# SH-03225-V0_5.net
KiCad netlist of a schematic drawn in Altium Designer
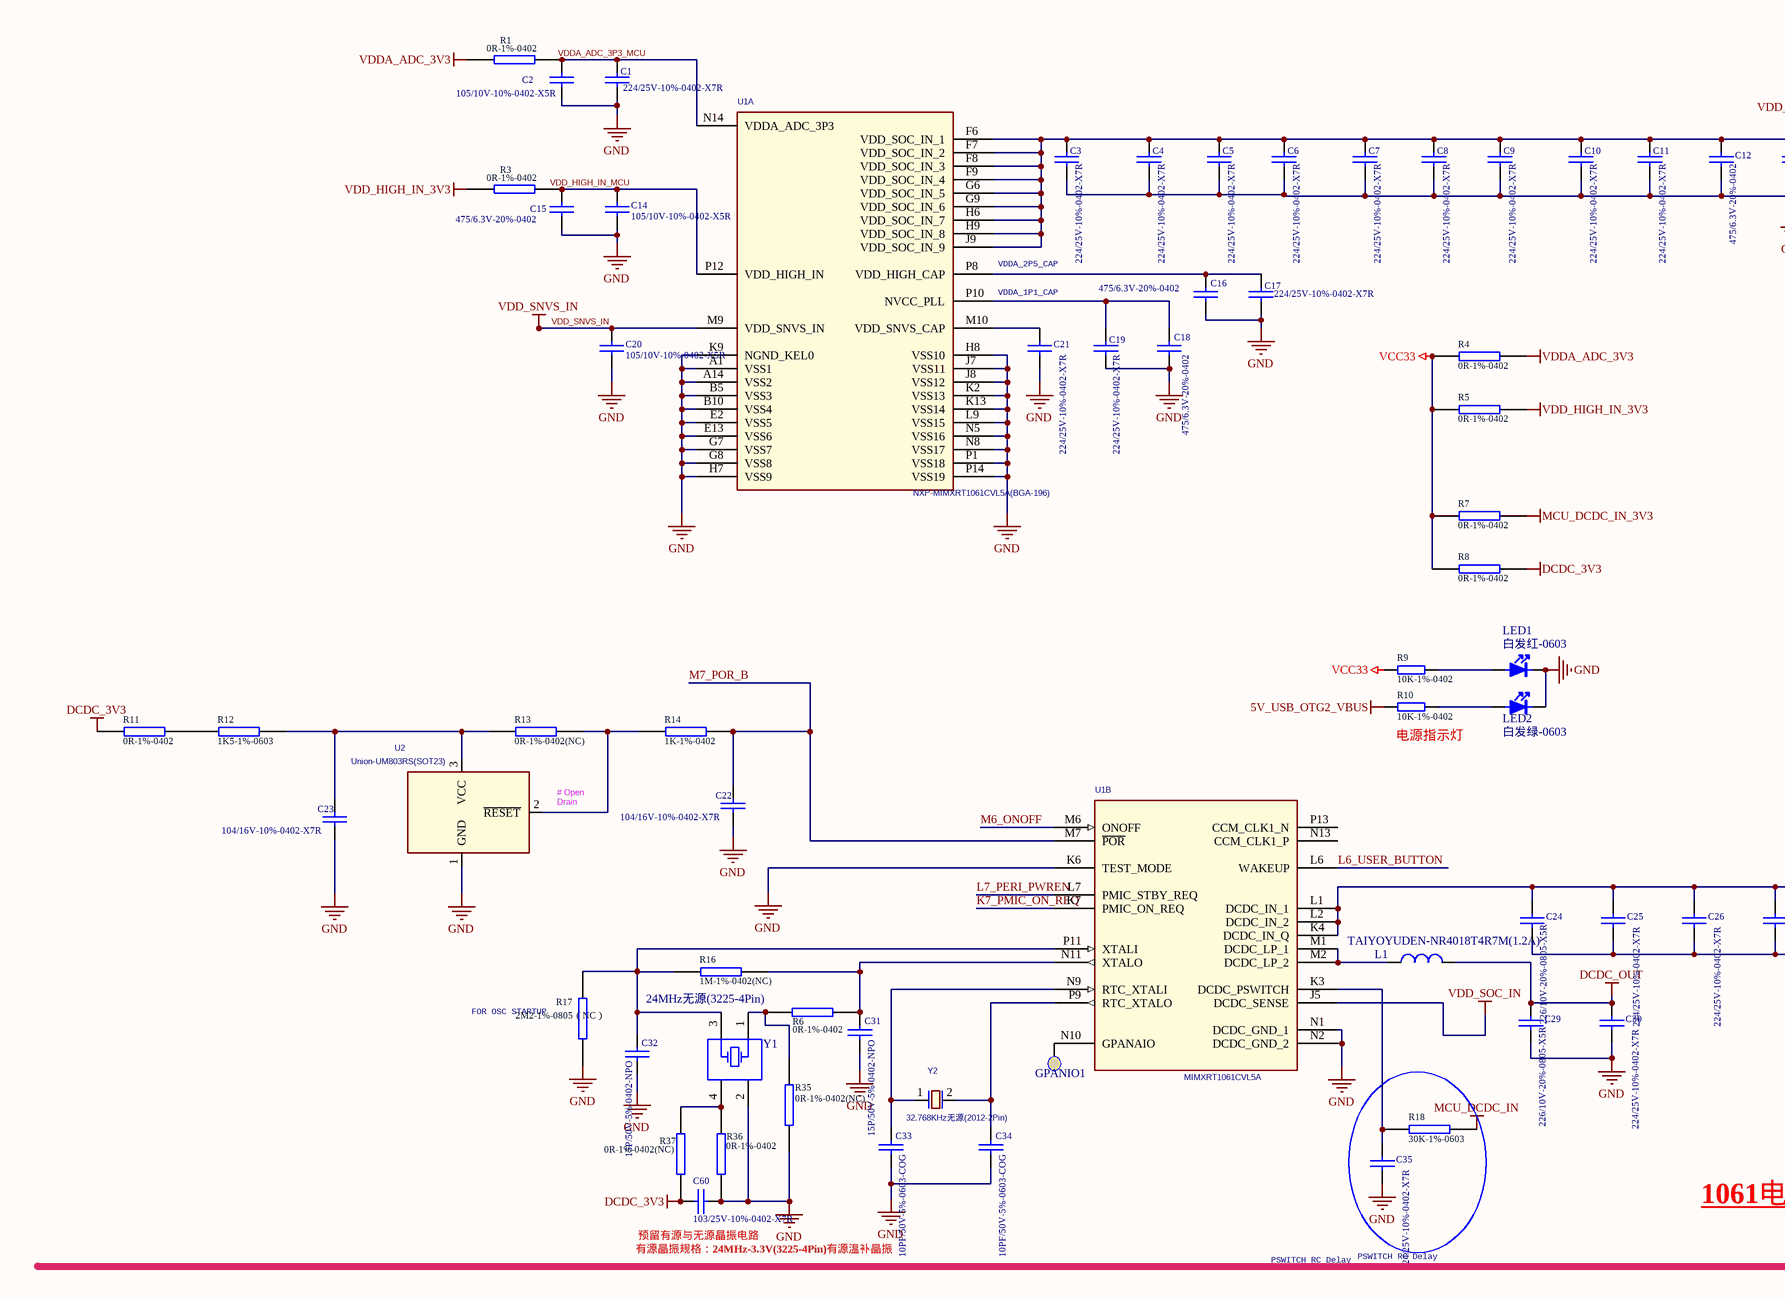
[diagram p0: SH-03225-V0.5.SchDoc, top left]
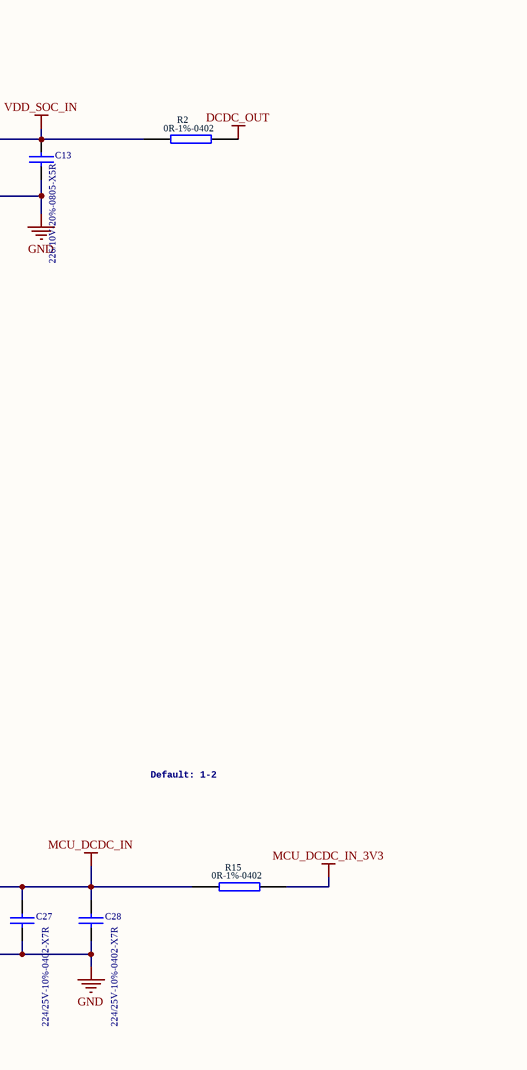
[diagram p1: SH-03225-V0.5.SchDoc, top middle]
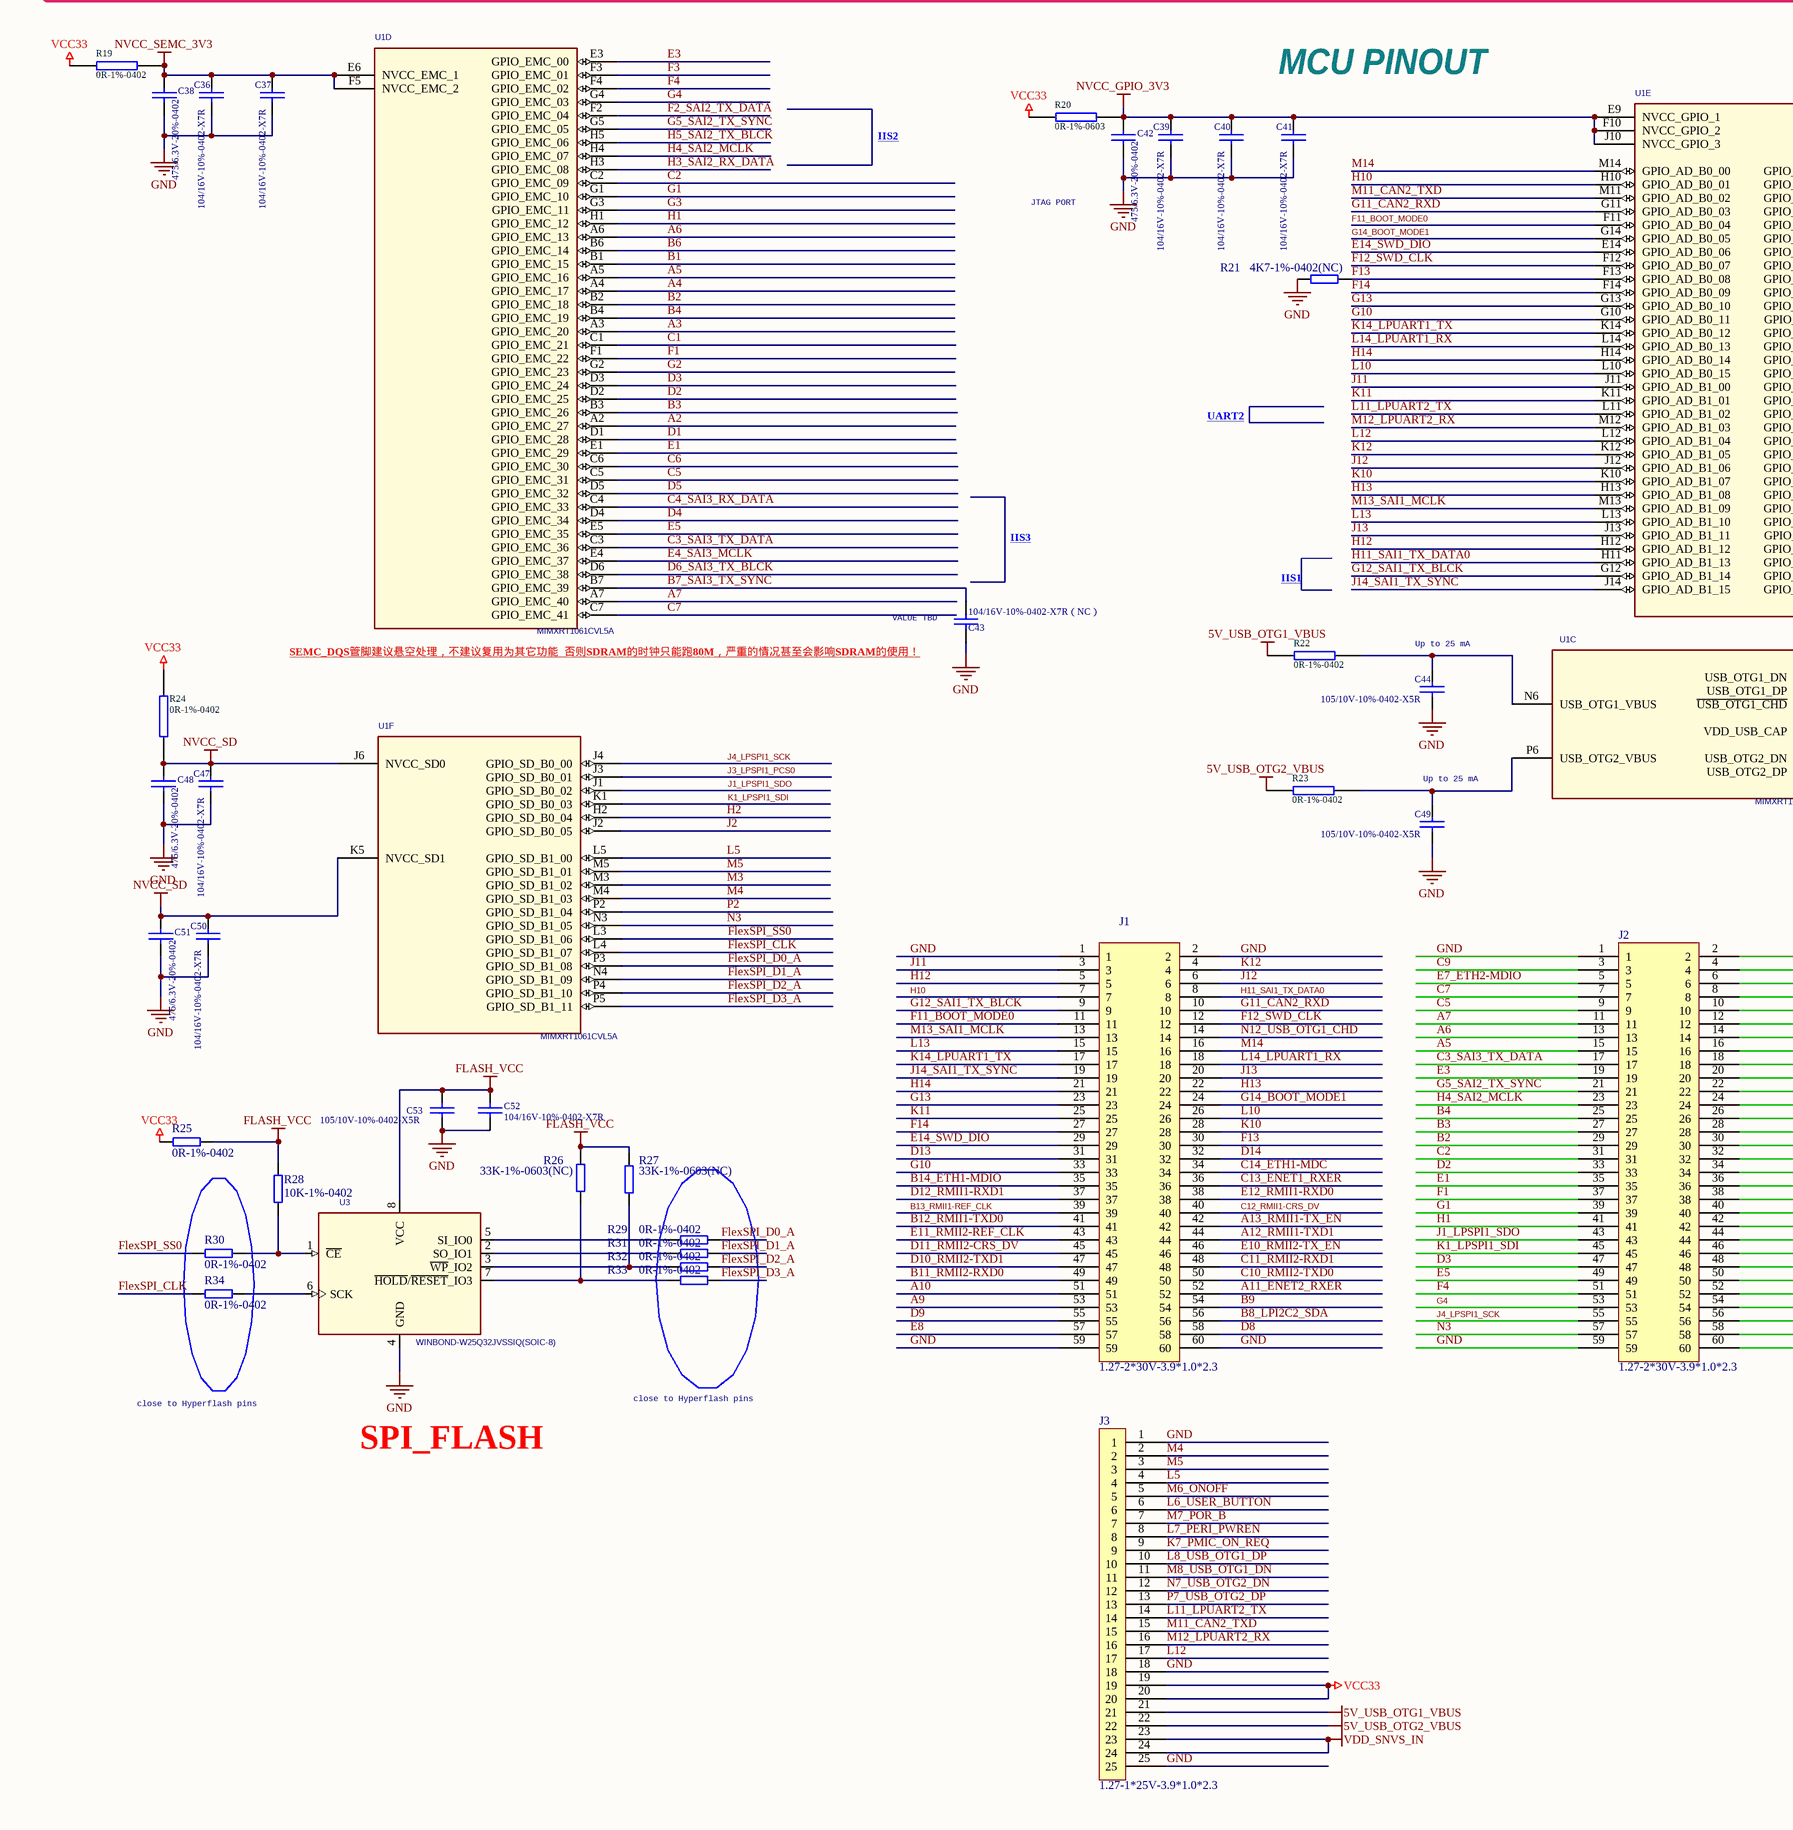
[diagram p2: SH-03225-V0.5.SchDoc, bottom left]
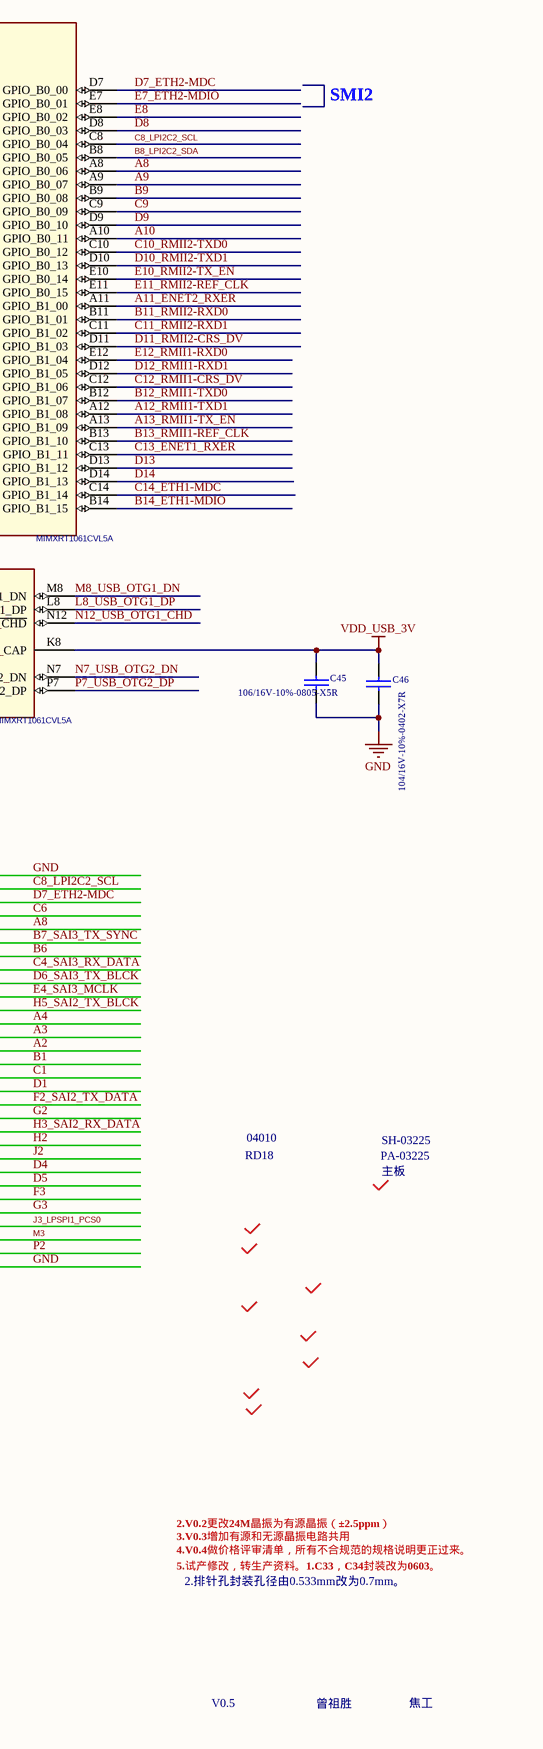
[diagram p3: SH-03225-V0.5.SchDoc, bottom middle]
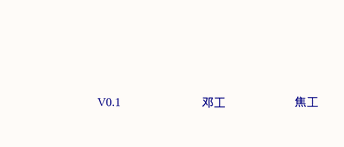
[diagram p4: SH-03225-V0.5.SchDoc, bottom right]

(export (version "E")
  (design (tool "Eeschema 10.0.6"))
  (components
    (comp (ref "C1")
      (value "224/25V-10%-0402-X7R")
      (footprint "BL-C0402")
      (description "Capacitor")
      (libsource (lib "*") (part "CAP"))
    )
    (comp (ref "C2")
      (value "105/10V-10%-0402-X5R")
      (footprint "BL-C0402")
      (description "Capacitor")
      (libsource (lib "*") (part "CAP"))
    )
    (comp (ref "C3")
      (value "224/25V-10%-0402-X7R")
      (footprint "BL-C0402")
      (description "Capacitor")
      (libsource (lib "*") (part "CAP"))
    )
    (comp (ref "C4")
      (value "224/25V-10%-0402-X7R")
      (footprint "BL-C0402")
      (description "Capacitor")
      (libsource (lib "*") (part "CAP"))
    )
    (comp (ref "C5")
      (value "224/25V-10%-0402-X7R")
      (footprint "BL-C0402")
      (description "Capacitor")
      (libsource (lib "*") (part "CAP"))
    )
    (comp (ref "C6")
      (value "224/25V-10%-0402-X7R")
      (footprint "BL-C0402")
      (description "Capacitor")
      (libsource (lib "*") (part "CAP"))
    )
    (comp (ref "C7")
      (value "224/25V-10%-0402-X7R")
      (footprint "BL-C0402")
      (description "Capacitor")
      (libsource (lib "*") (part "CAP"))
    )
    (comp (ref "C8")
      (value "224/25V-10%-0402-X7R")
      (footprint "BL-C0402")
      (description "Capacitor")
      (libsource (lib "*") (part "CAP"))
    )
    (comp (ref "C9")
      (value "224/25V-10%-0402-X7R")
      (footprint "BL-C0402")
      (description "Capacitor")
      (libsource (lib "*") (part "CAP"))
    )
    (comp (ref "C10")
      (value "224/25V-10%-0402-X7R")
      (footprint "BL-C0402")
      (description "Capacitor")
      (libsource (lib "*") (part "CAP"))
    )
    (comp (ref "C11")
      (value "224/25V-10%-0402-X7R")
      (footprint "BL-C0402")
      (description "Capacitor")
      (libsource (lib "*") (part "CAP"))
    )
    (comp (ref "C12")
      (value "475/6.3V-20%-0402")
      (footprint "BL-C0402")
      (description "Capacitor")
      (libsource (lib "*") (part "CAP"))
    )
    (comp (ref "C13")
      (value "226/10V-20%-0805-X5R")
      (footprint "BL-C0805")
      (description "Capacitor")
      (libsource (lib "*") (part "CAP"))
    )
    (comp (ref "C14")
      (value "105/10V-10%-0402-X5R")
      (footprint "BL-C0402")
      (description "Capacitor")
      (libsource (lib "*") (part "CAP"))
    )
    (comp (ref "C15")
      (value "475/6.3V-20%-0402")
      (footprint "BL-C0402")
      (description "Capacitor")
      (libsource (lib "*") (part "CAP"))
    )
    (comp (ref "C16")
      (value "475/6.3V-20%-0402")
      (footprint "BL-C0402")
      (description "Capacitor")
      (libsource (lib "*") (part "CAP"))
    )
    (comp (ref "C17")
      (value "224/25V-10%-0402-X7R")
      (footprint "BL-C0402")
      (description "Capacitor")
      (libsource (lib "*") (part "CAP"))
    )
    (comp (ref "C18")
      (value "475/6.3V-20%-0402")
      (footprint "BL-C0402")
      (description "Capacitor")
      (libsource (lib "*") (part "CAP"))
    )
    (comp (ref "C19")
      (value "224/25V-10%-0402-X7R")
      (footprint "BL-C0402")
      (description "Capacitor")
      (libsource (lib "*") (part "CAP"))
    )
    (comp (ref "C20")
      (value "105/10V-10%-0402-X5R")
      (footprint "BL-C0402")
      (description "Capacitor")
      (libsource (lib "*") (part "CAP"))
    )
    (comp (ref "C21")
      (value "224/25V-10%-0402-X7R")
      (footprint "BL-C0402")
      (description "Capacitor")
      (libsource (lib "*") (part "CAP"))
    )
    (comp (ref "C22")
      (value "104/16V-10%-0402-X7R")
      (footprint "BL-C0402")
      (description "Capacitor")
      (libsource (lib "*") (part "CAP"))
    )
    (comp (ref "C23")
      (value "104/16V-10%-0402-X7R")
      (footprint "BL-C0402")
      (description "Capacitor")
      (libsource (lib "*") (part "CAP"))
    )
    (comp (ref "C24")
      (value "226/10V-20%-0805-X5R")
      (footprint "BL-C0805")
      (description "Capacitor")
      (libsource (lib "*") (part "CAP"))
    )
    (comp (ref "C25")
      (value "224/25V-10%-0402-X7R")
      (footprint "BL-C0402")
      (description "Capacitor")
      (libsource (lib "*") (part "CAP"))
    )
    (comp (ref "C26")
      (value "224/25V-10%-0402-X7R")
      (footprint "BL-C0402")
      (description "Capacitor")
      (libsource (lib "*") (part "CAP"))
    )
    (comp (ref "C27")
      (value "224/25V-10%-0402-X7R")
      (footprint "BL-C0402")
      (description "Capacitor")
      (libsource (lib "*") (part "CAP"))
    )
    (comp (ref "C28")
      (value "224/25V-10%-0402-X7R")
      (footprint "BL-C0402")
      (description "Capacitor")
      (libsource (lib "*") (part "CAP"))
    )
    (comp (ref "C29")
      (value "226/10V-20%-0805-X5R")
      (footprint "BL-C0805")
      (description "Capacitor")
      (libsource (lib "*") (part "CAP"))
    )
    (comp (ref "C30")
      (value "224/25V-10%-0402-X7R")
      (footprint "BL-C0402")
      (description "Capacitor")
      (libsource (lib "*") (part "CAP"))
    )
    (comp (ref "C31")
      (value "15P/50V-5%-0402-NPO")
      (footprint "BL-C0402")
      (description "Capacitor")
      (libsource (lib "*") (part "CAP"))
    )
    (comp (ref "C32")
      (value "15P/50V-5%-0402-NPO")
      (footprint "BL-C0402")
      (description "Capacitor")
      (libsource (lib "*") (part "CAP"))
    )
    (comp (ref "C33")
      (value "10PF/50V-5%-0603-COG")
      (footprint "BL-C0603")
      (description "Capacitor")
      (libsource (lib "*") (part "CAP"))
    )
    (comp (ref "C34")
      (value "10PF/50V-5%-0603-COG")
      (footprint "BL-C0603")
      (description "Capacitor")
      (libsource (lib "*") (part "CAP"))
    )
    (comp (ref "C35")
      (value "224/25V-10%-0402-X7R")
      (footprint "BL-C0402")
      (description "Capacitor")
      (libsource (lib "*") (part "CAP"))
    )
    (comp (ref "C36")
      (value "104/16V-10%-0402-X7R")
      (footprint "BL-C0402")
      (description "Capacitor")
      (libsource (lib "*") (part "CAP"))
    )
    (comp (ref "C37")
      (value "104/16V-10%-0402-X7R")
      (footprint "BL-C0402")
      (description "Capacitor")
      (libsource (lib "*") (part "CAP"))
    )
    (comp (ref "C38")
      (value "475/6.3V-20%-0402")
      (footprint "BL-C0402")
      (description "Capacitor")
      (libsource (lib "*") (part "CAP"))
    )
    (comp (ref "C39")
      (value "104/16V-10%-0402-X7R")
      (footprint "BL-C0402")
      (description "Capacitor")
      (libsource (lib "*") (part "CAP"))
    )
    (comp (ref "C40")
      (value "104/16V-10%-0402-X7R")
      (footprint "BL-C0402")
      (description "Capacitor")
      (libsource (lib "*") (part "CAP"))
    )
    (comp (ref "C41")
      (value "104/16V-10%-0402-X7R")
      (footprint "BL-C0402")
      (description "Capacitor")
      (libsource (lib "*") (part "CAP"))
    )
    (comp (ref "C42")
      (value "475/6.3V-20%-0402")
      (footprint "BL-C0402")
      (description "Capacitor")
      (libsource (lib "*") (part "CAP"))
    )
    (comp (ref "C43")
      (value "104/16V-10%-0402-X7R（NC）")
      (footprint "BL-C0402")
      (description "Capacitor")
      (libsource (lib "*") (part "CAP"))
    )
    (comp (ref "C44")
      (value "105/10V-10%-0402-X5R")
      (footprint "BL-C0402")
      (description "Capacitor")
      (libsource (lib "*") (part "CAP"))
    )
    (comp (ref "C45")
      (value "106/16V-10%-0805-X5R")
      (footprint "BL-C0805")
      (description "Capacitor")
      (libsource (lib "*") (part "CAP"))
    )
    (comp (ref "C46")
      (value "104/16V-10%-0402-X7R")
      (footprint "BL-C0402")
      (description "Capacitor")
      (libsource (lib "*") (part "CAP"))
    )
    (comp (ref "C47")
      (value "104/16V-10%-0402-X7R")
      (footprint "BL-C0402")
      (description "Capacitor")
      (libsource (lib "*") (part "CAP"))
    )
    (comp (ref "C48")
      (value "475/6.3V-20%-0402")
      (footprint "BL-C0402")
      (description "Capacitor")
      (libsource (lib "*") (part "CAP"))
    )
    (comp (ref "C49")
      (value "105/10V-10%-0402-X5R")
      (footprint "BL-C0402")
      (description "Capacitor")
      (libsource (lib "*") (part "CAP"))
    )
    (comp (ref "C50")
      (value "104/16V-10%-0402-X7R")
      (footprint "BL-C0402")
      (description "Capacitor")
      (libsource (lib "*") (part "CAP"))
    )
    (comp (ref "C51")
      (value "475/6.3V-20%-0402")
      (footprint "BL-C0402")
      (description "Capacitor")
      (libsource (lib "*") (part "CAP"))
    )
    (comp (ref "C52")
      (value "104/16V-10%-0402-X7R")
      (footprint "BL-C0402")
      (description "Capacitor")
      (libsource (lib "*") (part "CAP"))
    )
    (comp (ref "C53")
      (value "105/10V-10%-0402-X5R")
      (footprint "BL-C0402")
      (description "Capacitor")
      (libsource (lib "*") (part "CAP"))
    )
    (comp (ref "C60")
      (value "103/25V-10%-0402-X7R")
      (footprint "BL-C0402")
      (description "Capacitor")
      (libsource (lib "*") (part "CAP"))
    )
    (comp (ref "GPANIO1") (value "测试点") (footprint "TP-1.0MM") (libsource (lib "*") (part "测试点")))
    (comp (ref "J1")
      (value "1.27-2*30V-3.9*1.0*2.3")
      (footprint "BL-1.27-2*30V-4.3*2.8-07")
      (libsource (lib "TJA1040T") (part "1.27-2*30V-4.3*2.8"))
    )
    (comp (ref "J2")
      (value "1.27-2*30V-3.9*1.0*2.3")
      (footprint "BL-1.27-2*30V-4.3*2.8-07")
      (libsource (lib "TJA1040T") (part "1.27-2*30V-4.3*2.8"))
    )
    (comp (ref "J3")
      (value "1.27-1*25V-3.9*1.0*2.3")
      (footprint "BL-1.27-1*25V")
      (libsource (lib "TJA1040T") (part "1.27-1*25V-4.3*2.8"))
    )
    (comp (ref "L1")
      (value "TAIYOYUDEN-NR4018T4R7M(1.2A)")
      (footprint "BL-NR4018T4R7M")
      (libsource (lib "视频处理器") (part "L"))
    )
    (comp (ref "LED1") (value "白发红-0603") (footprint "BL-LED-0603") (libsource (lib "*") (part "LED")))
    (comp (ref "LED2") (value "白发绿-0603") (footprint "BL-LED-0603") (libsource (lib "*") (part "LED")))
    (comp (ref "R1") (value "0R-1%-0402") (footprint "BL-R0402") (libsource (lib "*") (part "RES2")))
    (comp (ref "R2") (value "0R-1%-0402") (footprint "BL-R0402") (libsource (lib "*") (part "RES2")))
    (comp (ref "R3") (value "0R-1%-0402") (footprint "BL-R0402") (libsource (lib "*") (part "RES2")))
    (comp (ref "R4") (value "0R-1%-0402") (footprint "BL-R0402") (libsource (lib "*") (part "RES2")))
    (comp (ref "R5") (value "0R-1%-0402") (footprint "BL-R0402") (libsource (lib "*") (part "RES2")))
    (comp (ref "R6") (value "0R-1%-0402") (footprint "BL-R0402") (libsource (lib "*") (part "RES2")))
    (comp (ref "R7") (value "0R-1%-0402") (footprint "BL-R0402") (libsource (lib "*") (part "RES2")))
    (comp (ref "R8") (value "0R-1%-0402") (footprint "BL-R0402") (libsource (lib "*") (part "RES2")))
    (comp (ref "R9") (value "10K-1%-0402") (footprint "BL-R0402") (libsource (lib "") (part "RES2_1")))
    (comp (ref "R10") (value "10K-1%-0402") (footprint "BL-R0402") (libsource (lib "") (part "RES2_1")))
    (comp (ref "R11") (value "0R-1%-0402") (footprint "BL-R0402") (libsource (lib "*") (part "RES2")))
    (comp (ref "R12") (value "1K5-1%-0603") (footprint "BL-R0603") (libsource (lib "*") (part "RES2")))
    (comp (ref "R13") (value "0R-1%-0402(NC)") (footprint "BL-R0402") (libsource (lib "*") (part "RES2")))
    (comp (ref "R14") (value "1K-1%-0402") (footprint "BL-R0402") (libsource (lib "*") (part "RES2")))
    (comp (ref "R15") (value "0R-1%-0402") (footprint "BL-R0402") (libsource (lib "*") (part "RES2")))
    (comp (ref "R16") (value "1M-1%-0402(NC)") (footprint "BL-R0805") (libsource (lib "*") (part "RES2")))
    (comp (ref "R17") (value "2M2-1%-0805（NC）") (footprint "BL-R0805") (libsource (lib "*") (part "RES2")))
    (comp (ref "R18") (value "30K-1%-0603") (footprint "BL-R0603") (libsource (lib "*") (part "RES2")))
    (comp (ref "R19") (value "0R-1%-0402") (footprint "BL-R0402") (libsource (lib "*") (part "RES2")))
    (comp (ref "R20") (value "0R-1%-0603") (footprint "BL-R0603") (libsource (lib "*") (part "RES2")))
    (comp (ref "R21") (value "4K7-1%-0402(NC)") (footprint "BL-R0402") (libsource (lib "") (part "RES2_1")))
    (comp (ref "R22") (value "0R-1%-0402") (footprint "BL-R0402") (libsource (lib "*") (part "RES2")))
    (comp (ref "R23") (value "0R-1%-0402") (footprint "BL-R0402") (libsource (lib "*") (part "RES2")))
    (comp (ref "R24") (value "0R-1%-0402") (footprint "BL-R0402") (libsource (lib "*") (part "RES2")))
    (comp (ref "R25") (value "0R-1%-0402") (footprint "BL-R0402") (libsource (lib "") (part "RES2_1")))
    (comp (ref "R26") (value "33K-1%-0603(NC)") (footprint "BL-R0603") (libsource (lib "") (part "RES2_1")))
    (comp (ref "R27") (value "33K-1%-0603(NC)") (footprint "BL-R0603") (libsource (lib "") (part "RES2_1")))
    (comp (ref "R28") (value "10K-1%-0402") (footprint "BL-R0402") (libsource (lib "") (part "RES2_1")))
    (comp (ref "R29") (value "0R-1%-0402") (footprint "BL-R0402") (libsource (lib "") (part "RES2_1")))
    (comp (ref "R30") (value "0R-1%-0402") (footprint "BL-R0402") (libsource (lib "") (part "RES2_1")))
    (comp (ref "R31") (value "0R-1%-0402") (footprint "BL-R0402") (libsource (lib "") (part "RES2_1")))
    (comp (ref "R32") (value "0R-1%-0402") (footprint "BL-R0402") (libsource (lib "") (part "RES2_1")))
    (comp (ref "R33") (value "0R-1%-0402") (footprint "BL-R0402") (libsource (lib "") (part "RES2_1")))
    (comp (ref "R34") (value "0R-1%-0402") (footprint "BL-R0402") (libsource (lib "") (part "RES2_1")))
    (comp (ref "R35") (value "0R-1%-0402(NC)") (footprint "BL-R0402") (libsource (lib "*") (part "RES2")))
    (comp (ref "R36") (value "0R-1%-0402") (footprint "BL-R0402") (libsource (lib "*") (part "RES2")))
    (comp (ref "R37") (value "0R-1%-0402(NC)") (footprint "BL-R0402") (libsource (lib "*") (part "RES2")))
    (comp (ref "U1")
      (value "NXP-MIMXRT1061CVL5A(BGA-196)")
      (description "IC CPU ARM Cortex-M7 600MHZ 1.3V MAPBGA196")
      (libsource (lib "*") (part "IMX6_BGA_196P"))
    )
    (comp (ref "U2")
      (value "Union-UM803RS(SOT23)")
      (description "IC VOLT MONITOR 2.63V RST VTH 1-5.5V AUTO SOT-23")
      (libsource (lib "*") (part "SGM803_SOT23-3P"))
    )
    (comp (ref "U3")
      (value "WINBOND-W25Q32JVSSIQ(SOIC-8)")
      (description "IC MEM FLASH QPI 64Mb 1.65-1.95V SOIC8W")
      (libsource (lib "*") (part "25WP_8P"))
    )
    (comp (ref "Y1")
      (value "24MHz无源(3225-4Pin)")
      (footprint "BL-3225-4Pin")
      (description "贴片晶振")
      (libsource (lib "BL-DEVICE-SCH") (part "无源贴片晶振-4P"))
    )
    (comp (ref "Y2")
      (value "32.768KHz无源(2012-2Pin)")
      (description "XTAL 32.768KHZ 7PF 20PPM -- SMT")
      (libsource (lib "*") (part "CRYSTAL"))
    )
  )
  (nets
    (net (code "1") (name "/A2") (class "Default")
      (node (ref "J2") (pin "28") (pinfunction "28_28") (pintype "passive"))
      (node (ref "U1") (pin "A2") (pinfunction "GPIO_EMC_27_A2") (pintype "bidirectional"))
    )
    (net (code "2") (name "/A3") (class "Default")
      (node (ref "J2") (pin "26") (pinfunction "26_26") (pintype "passive"))
      (node (ref "U1") (pin "A3") (pinfunction "GPIO_EMC_20_A3") (pintype "bidirectional"))
    )
    (net (code "3") (name "/A4") (class "Default")
      (node (ref "J2") (pin "24") (pinfunction "24_24") (pintype "passive"))
      (node (ref "U1") (pin "A4") (pinfunction "GPIO_EMC_17_A4") (pintype "bidirectional"))
    )
    (net (code "4") (name "/A5") (class "Default")
      (node (ref "J2") (pin "15") (pinfunction "15_15") (pintype "passive"))
      (node (ref "U1") (pin "A5") (pinfunction "GPIO_EMC_16_A5") (pintype "bidirectional"))
    )
    (net (code "5") (name "/A6") (class "Default")
      (node (ref "J2") (pin "13") (pinfunction "13_13") (pintype "passive"))
      (node (ref "U1") (pin "A6") (pinfunction "GPIO_EMC_13_A6") (pintype "bidirectional"))
    )
    (net (code "6") (name "/A7") (class "Default")
      (node (ref "J2") (pin "11") (pinfunction "11_11") (pintype "passive"))
      (node (ref "U1") (pin "A7") (pinfunction "GPIO_EMC_40_A7") (pintype "bidirectional"))
    )
    (net (code "7") (name "/A8") (class "Default")
      (node (ref "J2") (pin "10") (pinfunction "10_10") (pintype "passive"))
      (node (ref "U1") (pin "A8") (pinfunction "GPIO_B0_06_A8") (pintype "bidirectional"))
    )
    (net (code "8") (name "/A9") (class "Default")
      (node (ref "J1") (pin "53") (pinfunction "53_53") (pintype "passive"))
      (node (ref "U1") (pin "A9") (pinfunction "GPIO_B0_07_A9") (pintype "bidirectional"))
    )
    (net (code "9") (name "/A10") (class "Default")
      (node (ref "J1") (pin "51") (pinfunction "51_51") (pintype "passive"))
      (node (ref "U1") (pin "A10") (pinfunction "GPIO_B0_11_A10") (pintype "bidirectional"))
    )
    (net (code "10") (name "/A11_ENET2_RXER") (class "Default")
      (node (ref "J1") (pin "52") (pinfunction "52_52") (pintype "passive"))
      (node (ref "U1") (pin "A11") (pinfunction "GPIO_B1_00_A11") (pintype "bidirectional"))
    )
    (net (code "11") (name "/A12_RMII1-TXD1") (class "Default")
      (node (ref "J1") (pin "44") (pinfunction "44_44") (pintype "passive"))
      (node (ref "U1") (pin "A12") (pinfunction "GPIO_B1_08_A12") (pintype "bidirectional"))
    )
    (net (code "12") (name "/A13_RMII1-TX_EN") (class "Default")
      (node (ref "J1") (pin "42") (pinfunction "42_42") (pintype "passive"))
      (node (ref "U1") (pin "A13") (pinfunction "GPIO_B1_09_A13") (pintype "bidirectional"))
    )
    (net (code "13") (name "/B1") (class "Default")
      (node (ref "J2") (pin "30") (pinfunction "30_30") (pintype "passive"))
      (node (ref "U1") (pin "B1") (pinfunction "GPIO_EMC_15_B1") (pintype "bidirectional"))
    )
    (net (code "14") (name "/B2") (class "Default")
      (node (ref "J2") (pin "29") (pinfunction "29_29") (pintype "passive"))
      (node (ref "U1") (pin "B2") (pinfunction "GPIO_EMC_18_B2") (pintype "bidirectional"))
    )
    (net (code "15") (name "/B3") (class "Default")
      (node (ref "J2") (pin "27") (pinfunction "27_27") (pintype "passive"))
      (node (ref "U1") (pin "B3") (pinfunction "GPIO_EMC_26_B3") (pintype "bidirectional"))
    )
    (net (code "16") (name "/B4") (class "Default")
      (node (ref "J2") (pin "25") (pinfunction "25_25") (pintype "passive"))
      (node (ref "U1") (pin "B4") (pinfunction "GPIO_EMC_19_B4") (pintype "bidirectional"))
    )
    (net (code "17") (name "/B6") (class "Default")
      (node (ref "J2") (pin "14") (pinfunction "14_14") (pintype "passive"))
      (node (ref "U1") (pin "B6") (pinfunction "GPIO_EMC_14_B6") (pintype "bidirectional"))
    )
    (net (code "18") (name "/B7_SAI3_TX_SYNC") (class "Default")
      (node (ref "C43") (pin "2") (pinfunction "2_2") (pintype "passive"))
      (node (ref "J2") (pin "12") (pinfunction "12_12") (pintype "passive"))
      (node (ref "U1") (pin "B7") (pinfunction "GPIO_EMC_39_B7") (pintype "bidirectional"))
    )
    (net (code "19") (name "/B8_LPI2C2_SDA") (class "Default")
      (node (ref "J1") (pin "56") (pinfunction "56_56") (pintype "passive"))
      (node (ref "U1") (pin "B8") (pinfunction "GPIO_B0_05_B8") (pintype "bidirectional"))
    )
    (net (code "20") (name "/B9") (class "Default")
      (node (ref "J1") (pin "54") (pinfunction "54_54") (pintype "passive"))
      (node (ref "U1") (pin "B9") (pinfunction "GPIO_B0_08_B9") (pintype "bidirectional"))
    )
    (net (code "21") (name "/B11_RMII2-RXD0") (class "Default")
      (node (ref "J1") (pin "49") (pinfunction "49_49") (pintype "passive"))
      (node (ref "U1") (pin "B11") (pinfunction "GPIO_B1_01_B11") (pintype "bidirectional"))
    )
    (net (code "22") (name "/B12_RMII1-TXD0") (class "Default")
      (node (ref "J1") (pin "41") (pinfunction "41_41") (pintype "passive"))
      (node (ref "U1") (pin "B12") (pinfunction "GPIO_B1_07_B12") (pintype "bidirectional"))
    )
    (net (code "23") (name "/B13_RMII1-REF_CLK") (class "Default")
      (node (ref "J1") (pin "39") (pinfunction "39_39") (pintype "passive"))
      (node (ref "U1") (pin "B13") (pinfunction "GPIO_B1_10_B13") (pintype "bidirectional"))
    )
    (net (code "24") (name "/B14_ETH1-MDIO") (class "Default")
      (node (ref "J1") (pin "35") (pinfunction "35_35") (pintype "passive"))
      (node (ref "U1") (pin "B14") (pinfunction "GPIO_B1_15_B14") (pintype "bidirectional"))
    )
    (net (code "25") (name "/C1") (class "Default")
      (node (ref "J2") (pin "32") (pinfunction "32_32") (pintype "passive"))
      (node (ref "U1") (pin "C1") (pinfunction "GPIO_EMC_21_C1") (pintype "bidirectional"))
    )
    (net (code "26") (name "/C2") (class "Default")
      (node (ref "J2") (pin "31") (pinfunction "31_31") (pintype "passive"))
      (node (ref "U1") (pin "C2") (pinfunction "GPIO_EMC_09_C2") (pintype "bidirectional"))
    )
    (net (code "27") (name "/C3_SAI3_TX_DATA") (class "Default")
      (node (ref "J2") (pin "17") (pinfunction "17_17") (pintype "passive"))
      (node (ref "U1") (pin "C3") (pinfunction "GPIO_EMC_36_C3") (pintype "bidirectional"))
    )
    (net (code "28") (name "/C4_SAI3_RX_DATA") (class "Default")
      (node (ref "J2") (pin "16") (pinfunction "16_16") (pintype "passive"))
      (node (ref "U1") (pin "C4") (pinfunction "GPIO_EMC_33_C4") (pintype "bidirectional"))
    )
    (net (code "29") (name "/C5") (class "Default")
      (node (ref "J2") (pin "9") (pinfunction "9_9") (pintype "passive"))
      (node (ref "U1") (pin "C5") (pinfunction "GPIO_EMC_31_C5") (pintype "bidirectional"))
    )
    (net (code "30") (name "/C6") (class "Default")
      (node (ref "J2") (pin "8") (pinfunction "8_8") (pintype "passive"))
      (node (ref "U1") (pin "C6") (pinfunction "GPIO_EMC_30_C6") (pintype "bidirectional"))
    )
    (net (code "31") (name "/C7") (class "Default")
      (node (ref "J2") (pin "7") (pinfunction "7_7") (pintype "passive"))
      (node (ref "U1") (pin "C7") (pinfunction "GPIO_EMC_41_C7") (pintype "bidirectional"))
    )
    (net (code "32") (name "/C8_LPI2C2_SCL") (class "Default")
      (node (ref "J2") (pin "4") (pinfunction "4_4") (pintype "passive"))
      (node (ref "U1") (pin "C8") (pinfunction "GPIO_B0_04_C8") (pintype "bidirectional"))
    )
    (net (code "33") (name "/C9") (class "Default")
      (node (ref "J2") (pin "3") (pinfunction "3_3") (pintype "passive"))
      (node (ref "U1") (pin "C9") (pinfunction "GPIO_B0_09_C9") (pintype "bidirectional"))
    )
    (net (code "34") (name "/C10_RMII2-TXD0") (class "Default")
      (node (ref "J1") (pin "50") (pinfunction "50_50") (pintype "passive"))
      (node (ref "U1") (pin "C10") (pinfunction "GPIO_B0_12_C10") (pintype "bidirectional"))
    )
    (net (code "35") (name "/C11_RMII2-RXD1") (class "Default")
      (node (ref "J1") (pin "48") (pinfunction "48_48") (pintype "passive"))
      (node (ref "U1") (pin "C11") (pinfunction "GPIO_B1_02_C11") (pintype "bidirectional"))
    )
    (net (code "36") (name "/C12_RMII1-CRS_DV") (class "Default")
      (node (ref "J1") (pin "40") (pinfunction "40_40") (pintype "passive"))
      (node (ref "U1") (pin "C12") (pinfunction "GPIO_B1_06_C12") (pintype "bidirectional"))
    )
    (net (code "37") (name "/C13_ENET1_RXER") (class "Default")
      (node (ref "J1") (pin "36") (pinfunction "36_36") (pintype "passive"))
      (node (ref "U1") (pin "C13") (pinfunction "GPIO_B1_11_C13") (pintype "bidirectional"))
    )
    (net (code "38") (name "/C14_ETH1-MDC") (class "Default")
      (node (ref "J1") (pin "34") (pinfunction "34_34") (pintype "passive"))
      (node (ref "U1") (pin "C14") (pinfunction "GPIO_B1_14_C14") (pintype "bidirectional"))
    )
    (net (code "39") (name "/D1") (class "Default")
      (node (ref "J2") (pin "34") (pinfunction "34_34") (pintype "passive"))
      (node (ref "U1") (pin "D1") (pinfunction "GPIO_EMC_28_D1") (pintype "bidirectional"))
    )
    (net (code "40") (name "/D2") (class "Default")
      (node (ref "J2") (pin "33") (pinfunction "33_33") (pintype "passive"))
      (node (ref "U1") (pin "D2") (pinfunction "GPIO_EMC_25_D2") (pintype "bidirectional"))
    )
    (net (code "41") (name "/D3") (class "Default")
      (node (ref "J2") (pin "47") (pinfunction "47_47") (pintype "passive"))
      (node (ref "U1") (pin "D3") (pinfunction "GPIO_EMC_24_D3") (pintype "bidirectional"))
    )
    (net (code "42") (name "/D4") (class "Default")
      (node (ref "J2") (pin "46") (pinfunction "46_46") (pintype "passive"))
      (node (ref "U1") (pin "D4") (pinfunction "GPIO_EMC_34_D4") (pintype "bidirectional"))
    )
    (net (code "43") (name "/D5") (class "Default")
      (node (ref "J2") (pin "48") (pinfunction "48_48") (pintype "passive"))
      (node (ref "U1") (pin "D5") (pinfunction "GPIO_EMC_32_D5") (pintype "bidirectional"))
    )
    (net (code "44") (name "/D6_SAI3_TX_BLCK") (class "Default")
      (node (ref "J2") (pin "18") (pinfunction "18_18") (pintype "passive"))
      (node (ref "U1") (pin "D6") (pinfunction "GPIO_EMC_38_D6") (pintype "bidirectional"))
    )
    (net (code "45") (name "/D7_ETH2-MDC") (class "Default")
      (node (ref "J2") (pin "6") (pinfunction "6_6") (pintype "passive"))
      (node (ref "U1") (pin "D7") (pinfunction "GPIO_B0_00_D7") (pintype "bidirectional"))
    )
    (net (code "46") (name "/D8") (class "Default")
      (node (ref "J1") (pin "58") (pinfunction "58_58") (pintype "passive"))
      (node (ref "U1") (pin "D8") (pinfunction "GPIO_B0_03_D8") (pintype "bidirectional"))
    )
    (net (code "47") (name "/D9") (class "Default")
      (node (ref "J1") (pin "55") (pinfunction "55_55") (pintype "passive"))
      (node (ref "U1") (pin "D9") (pinfunction "GPIO_B0_10_D9") (pintype "bidirectional"))
    )
    (net (code "48") (name "/D10_RMII2-TXD1") (class "Default")
      (node (ref "J1") (pin "47") (pinfunction "47_47") (pintype "passive"))
      (node (ref "U1") (pin "D10") (pinfunction "GPIO_B0_13_D10") (pintype "bidirectional"))
    )
    (net (code "49") (name "/D11_RMII2-CRS_DV") (class "Default")
      (node (ref "J1") (pin "45") (pinfunction "45_45") (pintype "passive"))
      (node (ref "U1") (pin "D11") (pinfunction "GPIO_B1_03_D11") (pintype "bidirectional"))
    )
    (net (code "50") (name "/D12_RMII1-RXD1") (class "Default")
      (node (ref "J1") (pin "37") (pinfunction "37_37") (pintype "passive"))
      (node (ref "U1") (pin "D12") (pinfunction "GPIO_B1_05_D12") (pintype "bidirectional"))
    )
    (net (code "51") (name "/D13") (class "Default")
      (node (ref "J1") (pin "31") (pinfunction "31_31") (pintype "passive"))
      (node (ref "U1") (pin "D13") (pinfunction "GPIO_B1_12_D13") (pintype "bidirectional"))
    )
    (net (code "52") (name "/D14") (class "Default")
      (node (ref "J1") (pin "32") (pinfunction "32_32") (pintype "passive"))
      (node (ref "U1") (pin "D14") (pinfunction "GPIO_B1_13_D14") (pintype "bidirectional"))
    )
    (net (code "53") (name "/E1") (class "Default")
      (node (ref "J2") (pin "35") (pinfunction "35_35") (pintype "passive"))
      (node (ref "U1") (pin "E1") (pinfunction "GPIO_EMC_29_E1") (pintype "bidirectional"))
    )
    (net (code "54") (name "/E3") (class "Default")
      (node (ref "J2") (pin "19") (pinfunction "19_19") (pintype "passive"))
      (node (ref "U1") (pin "E3") (pinfunction "GPIO_EMC_00_E3") (pintype "bidirectional"))
    )
    (net (code "55") (name "/E4_SAI3_MCLK") (class "Default")
      (node (ref "J2") (pin "20") (pinfunction "20_20") (pintype "passive"))
      (node (ref "U1") (pin "E4") (pinfunction "GPIO_EMC_37_E4") (pintype "bidirectional"))
    )
    (net (code "56") (name "/E5") (class "Default")
      (node (ref "J2") (pin "49") (pinfunction "49_49") (pintype "passive"))
      (node (ref "U1") (pin "E5") (pinfunction "GPIO_EMC_35_E5") (pintype "bidirectional"))
    )
    (net (code "57") (name "/E7_ETH2-MDIO") (class "Default")
      (node (ref "J2") (pin "5") (pinfunction "5_5") (pintype "passive"))
      (node (ref "U1") (pin "E7") (pinfunction "GPIO_B0_01_E7") (pintype "bidirectional"))
    )
    (net (code "58") (name "/E8") (class "Default")
      (node (ref "J1") (pin "57") (pinfunction "57_57") (pintype "passive"))
      (node (ref "U1") (pin "E8") (pinfunction "GPIO_B0_02_E8") (pintype "bidirectional"))
    )
    (net (code "59") (name "/E10_RMII2-TX_EN") (class "Default")
      (node (ref "J1") (pin "46") (pinfunction "46_46") (pintype "passive"))
      (node (ref "U1") (pin "E10") (pinfunction "GPIO_B0_14_E10") (pintype "bidirectional"))
    )
    (net (code "60") (name "/E11_RMII2-REF_CLK") (class "Default")
      (node (ref "J1") (pin "43") (pinfunction "43_43") (pintype "passive"))
      (node (ref "U1") (pin "E11") (pinfunction "GPIO_B0_15_E11") (pintype "bidirectional"))
    )
    (net (code "61") (name "/E12_RMII1-RXD0") (class "Default")
      (node (ref "J1") (pin "38") (pinfunction "38_38") (pintype "passive"))
      (node (ref "U1") (pin "E12") (pinfunction "GPIO_B1_04_E12") (pintype "bidirectional"))
    )
    (net (code "62") (name "/E14_SWD_DIO") (class "Default")
      (node (ref "J1") (pin "29") (pinfunction "29_29") (pintype "passive"))
      (node (ref "U1") (pin "E14") (pinfunction "GPIO_AD_B0_06_E14") (pintype "bidirectional"))
    )
    (net (code "63") (name "/F1") (class "Default")
      (node (ref "J2") (pin "37") (pinfunction "37_37") (pintype "passive"))
      (node (ref "U1") (pin "F1") (pinfunction "GPIO_EMC_22_F1") (pintype "bidirectional"))
    )
    (net (code "64") (name "/F2_SAI2_TX_DATA") (class "Default")
      (node (ref "J2") (pin "36") (pinfunction "36_36") (pintype "passive"))
      (node (ref "U1") (pin "F2") (pinfunction "GPIO_EMC_04_F2") (pintype "bidirectional"))
    )
    (net (code "65") (name "/F3") (class "Default")
      (node (ref "J2") (pin "50") (pinfunction "50_50") (pintype "passive"))
      (node (ref "U1") (pin "F3") (pinfunction "GPIO_EMC_01_F3") (pintype "bidirectional"))
    )
    (net (code "66") (name "/F4") (class "Default")
      (node (ref "J2") (pin "51") (pinfunction "51_51") (pintype "passive"))
      (node (ref "U1") (pin "F4") (pinfunction "GPIO_EMC_02_F4") (pintype "bidirectional"))
    )
    (net (code "67") (name "/F11_BOOT_MODE0") (class "Default")
      (node (ref "J1") (pin "11") (pinfunction "11_11") (pintype "passive"))
      (node (ref "U1") (pin "F11") (pinfunction "GPIO_AD_B0_04_F11") (pintype "bidirectional"))
    )
    (net (code "68") (name "/F12_SWD_CLK") (class "Default")
      (node (ref "J1") (pin "12") (pinfunction "12_12") (pintype "passive"))
      (node (ref "U1") (pin "F12") (pinfunction "GPIO_AD_B0_07_F12") (pintype "bidirectional"))
    )
    (net (code "69") (name "/F13") (class "Default")
      (node (ref "J1") (pin "30") (pinfunction "30_30") (pintype "passive"))
      (node (ref "R21") (pin "2") (pinfunction "2_2") (pintype "passive"))
      (node (ref "U1") (pin "F13") (pinfunction "GPIO_AD_B0_08_F13") (pintype "bidirectional"))
    )
    (net (code "70") (name "/F14") (class "Default")
      (node (ref "J1") (pin "27") (pinfunction "27_27") (pintype "passive"))
      (node (ref "U1") (pin "F14") (pinfunction "GPIO_AD_B0_09_F14") (pintype "bidirectional"))
    )
    (net (code "71") (name "/FlexSPI_CLK") (class "Default")
      (node (ref "R34") (pin "1") (pinfunction "1_1") (pintype "passive"))
      (node (ref "U1") (pin "L4") (pinfunction "GPIO_SD_B1_07_L4") (pintype "bidirectional"))
    )
    (net (code "72") (name "/FlexSPI_D0_A") (class "Default")
      (node (ref "R29") (pin "2") (pinfunction "2_2") (pintype "passive"))
      (node (ref "U1") (pin "P3") (pinfunction "GPIO_SD_B1_08_P3") (pintype "bidirectional"))
    )
    (net (code "73") (name "/FlexSPI_D1_A") (class "Default")
      (node (ref "R31") (pin "2") (pinfunction "2_2") (pintype "passive"))
      (node (ref "U1") (pin "N4") (pinfunction "GPIO_SD_B1_09_N4") (pintype "bidirectional"))
    )
    (net (code "74") (name "/FlexSPI_D2_A") (class "Default")
      (node (ref "R32") (pin "2") (pinfunction "2_2") (pintype "passive"))
      (node (ref "U1") (pin "P4") (pinfunction "GPIO_SD_B1_10_P4") (pintype "bidirectional"))
    )
    (net (code "75") (name "/FlexSPI_D3_A") (class "Default")
      (node (ref "R33") (pin "2") (pinfunction "2_2") (pintype "passive"))
      (node (ref "U1") (pin "P5") (pinfunction "GPIO_SD_B1_11_P5") (pintype "bidirectional"))
    )
    (net (code "76") (name "/FlexSPI_SS0") (class "Default")
      (node (ref "R30") (pin "1") (pinfunction "1_1") (pintype "passive"))
      (node (ref "U1") (pin "L3") (pinfunction "GPIO_SD_B1_06_L3") (pintype "bidirectional"))
    )
    (net (code "77") (name "/G1") (class "Default")
      (node (ref "J2") (pin "39") (pinfunction "39_39") (pintype "passive"))
      (node (ref "U1") (pin "G1") (pinfunction "GPIO_EMC_10_G1") (pintype "bidirectional"))
    )
    (net (code "78") (name "/G2") (class "Default")
      (node (ref "J2") (pin "38") (pinfunction "38_38") (pintype "passive"))
      (node (ref "U1") (pin "G2") (pinfunction "GPIO_EMC_23_G2") (pintype "bidirectional"))
    )
    (net (code "79") (name "/G3") (class "Default")
      (node (ref "J2") (pin "52") (pinfunction "52_52") (pintype "passive"))
      (node (ref "U1") (pin "G3") (pinfunction "GPIO_EMC_11_G3") (pintype "bidirectional"))
    )
    (net (code "80") (name "/G4") (class "Default")
      (node (ref "J2") (pin "53") (pinfunction "53_53") (pintype "passive"))
      (node (ref "U1") (pin "G4") (pinfunction "GPIO_EMC_03_G4") (pintype "bidirectional"))
    )
    (net (code "81") (name "/G5_SAI2_TX_SYNC") (class "Default")
      (node (ref "J2") (pin "21") (pinfunction "21_21") (pintype "passive"))
      (node (ref "U1") (pin "G5") (pinfunction "GPIO_EMC_05_G5") (pintype "bidirectional"))
    )
    (net (code "82") (name "/G10") (class "Default")
      (node (ref "J1") (pin "33") (pinfunction "33_33") (pintype "passive"))
      (node (ref "U1") (pin "G10") (pinfunction "GPIO_AD_B0_11_G10") (pintype "bidirectional"))
    )
    (net (code "83") (name "/G11_CAN2_RXD") (class "Default")
      (node (ref "J1") (pin "10") (pinfunction "10_10") (pintype "passive"))
      (node (ref "U1") (pin "G11") (pinfunction "GPIO_AD_B0_03_G11") (pintype "bidirectional"))
    )
    (net (code "84") (name "/G12_SAI1_TX_BLCK") (class "Default")
      (node (ref "J1") (pin "9") (pinfunction "9_9") (pintype "passive"))
      (node (ref "U1") (pin "G12") (pinfunction "GPIO_AD_B1_14_G12") (pintype "bidirectional"))
    )
    (net (code "85") (name "/G13") (class "Default")
      (node (ref "J1") (pin "23") (pinfunction "23_23") (pintype "passive"))
      (node (ref "U1") (pin "G13") (pinfunction "GPIO_AD_B0_10_G13") (pintype "bidirectional"))
    )
    (net (code "86") (name "/G14_BOOT_MODE1") (class "Default")
      (node (ref "J1") (pin "24") (pinfunction "24_24") (pintype "passive"))
      (node (ref "U1") (pin "G14") (pinfunction "GPIO_AD_B0_05_G14") (pintype "bidirectional"))
    )
    (net (code "87") (name "/H1") (class "Default")
      (node (ref "J2") (pin "41") (pinfunction "41_41") (pintype "passive"))
      (node (ref "U1") (pin "H1") (pinfunction "GPIO_EMC_12_H1") (pintype "bidirectional"))
    )
    (net (code "88") (name "/H2") (class "Default")
      (node (ref "J2") (pin "42") (pinfunction "42_42") (pintype "passive"))
      (node (ref "U1") (pin "H2") (pinfunction "GPIO_SD_B0_04_H2") (pintype "bidirectional"))
    )
    (net (code "89") (name "/H3_SAI2_RX_DATA") (class "Default")
      (node (ref "J2") (pin "40") (pinfunction "40_40") (pintype "passive"))
      (node (ref "U1") (pin "H3") (pinfunction "GPIO_EMC_08_H3") (pintype "bidirectional"))
    )
    (net (code "90") (name "/H4_SAI2_MCLK") (class "Default")
      (node (ref "J2") (pin "23") (pinfunction "23_23") (pintype "passive"))
      (node (ref "U1") (pin "H4") (pinfunction "GPIO_EMC_07_H4") (pintype "bidirectional"))
    )
    (net (code "91") (name "/H5_SAI2_TX_BLCK") (class "Default")
      (node (ref "J2") (pin "22") (pinfunction "22_22") (pintype "passive"))
      (node (ref "U1") (pin "H5") (pinfunction "GPIO_EMC_06_H5") (pintype "bidirectional"))
    )
    (net (code "92") (name "/H10") (class "Default")
      (node (ref "J1") (pin "7") (pinfunction "7_7") (pintype "passive"))
      (node (ref "U1") (pin "H10") (pinfunction "GPIO_AD_B0_01_H10") (pintype "bidirectional"))
    )
    (net (code "93") (name "/H11_SAI1_TX_DATA0") (class "Default")
      (node (ref "J1") (pin "8") (pinfunction "8_8") (pintype "passive"))
      (node (ref "U1") (pin "H11") (pinfunction "GPIO_AD_B1_13_H11") (pintype "bidirectional"))
    )
    (net (code "94") (name "/H12") (class "Default")
      (node (ref "J1") (pin "5") (pinfunction "5_5") (pintype "passive"))
      (node (ref "U1") (pin "H12") (pinfunction "GPIO_AD_B1_12_H12") (pintype "bidirectional"))
    )
    (net (code "95") (name "/H13") (class "Default")
      (node (ref "J1") (pin "22") (pinfunction "22_22") (pintype "passive"))
      (node (ref "U1") (pin "H13") (pinfunction "GPIO_AD_B1_08_H13") (pintype "bidirectional"))
    )
    (net (code "96") (name "/H14") (class "Default")
      (node (ref "J1") (pin "21") (pinfunction "21_21") (pintype "passive"))
      (node (ref "U1") (pin "H14") (pinfunction "GPIO_AD_B0_14_H14") (pintype "bidirectional"))
    )
    (net (code "97") (name "/J1_LPSPI1_SDO") (class "Default")
      (node (ref "J2") (pin "43") (pinfunction "43_43") (pintype "passive"))
      (node (ref "U1") (pin "J1") (pinfunction "GPIO_SD_B0_02_J1") (pintype "bidirectional"))
    )
    (net (code "98") (name "/J2") (class "Default")
      (node (ref "J2") (pin "44") (pinfunction "44_44") (pintype "passive"))
      (node (ref "U1") (pin "J2") (pinfunction "GPIO_SD_B0_05_J2") (pintype "bidirectional"))
    )
    (net (code "99") (name "/J3_LPSPI1_PCS0") (class "Default")
      (node (ref "J2") (pin "54") (pinfunction "54_54") (pintype "passive"))
      (node (ref "U1") (pin "J3") (pinfunction "GPIO_SD_B0_01_J3") (pintype "bidirectional"))
    )
    (net (code "100") (name "/J4_LPSPI1_SCK") (class "Default")
      (node (ref "J2") (pin "55") (pinfunction "55_55") (pintype "passive"))
      (node (ref "U1") (pin "J4") (pinfunction "GPIO_SD_B0_00_J4") (pintype "bidirectional"))
    )
    (net (code "101") (name "/J11") (class "Default")
      (node (ref "J1") (pin "3") (pinfunction "3_3") (pintype "passive"))
      (node (ref "U1") (pin "J11") (pinfunction "GPIO_AD_B1_00_J11") (pintype "bidirectional"))
    )
    (net (code "102") (name "/J12") (class "Default")
      (node (ref "J1") (pin "6") (pinfunction "6_6") (pintype "passive"))
      (node (ref "U1") (pin "J12") (pinfunction "GPIO_AD_B1_06_J12") (pintype "bidirectional"))
    )
    (net (code "103") (name "/J13") (class "Default")
      (node (ref "J1") (pin "20") (pinfunction "20_20") (pintype "passive"))
      (node (ref "U1") (pin "J13") (pinfunction "GPIO_AD_B1_11_J13") (pintype "bidirectional"))
    )
    (net (code "104") (name "/J14_SAI1_TX_SYNC") (class "Default")
      (node (ref "J1") (pin "19") (pinfunction "19_19") (pintype "passive"))
      (node (ref "U1") (pin "J14") (pinfunction "GPIO_AD_B1_15_J14") (pintype "bidirectional"))
    )
    (net (code "105") (name "/K1_LPSPI1_SDI") (class "Default")
      (node (ref "J2") (pin "45") (pinfunction "45_45") (pintype "passive"))
      (node (ref "U1") (pin "K1") (pinfunction "GPIO_SD_B0_03_K1") (pintype "bidirectional"))
    )
    (net (code "106") (name "/K7_PMIC_ON_REQ") (class "Default")
      (node (ref "J3") (pin "9") (pinfunction "9_9") (pintype "passive"))
      (node (ref "U1") (pin "K7") (pinfunction "PMIC_ON_REQ_K7") (pintype "passive"))
    )
    (net (code "107") (name "/K10") (class "Default")
      (node (ref "J1") (pin "28") (pinfunction "28_28") (pintype "passive"))
      (node (ref "U1") (pin "K10") (pinfunction "GPIO_AD_B1_07_K10") (pintype "bidirectional"))
    )
    (net (code "108") (name "/K11") (class "Default")
      (node (ref "J1") (pin "25") (pinfunction "25_25") (pintype "passive"))
      (node (ref "U1") (pin "K11") (pinfunction "GPIO_AD_B1_01_K11") (pintype "bidirectional"))
    )
    (net (code "109") (name "/K12") (class "Default")
      (node (ref "J1") (pin "4") (pinfunction "4_4") (pintype "passive"))
      (node (ref "U1") (pin "K12") (pinfunction "GPIO_AD_B1_05_K12") (pintype "bidirectional"))
    )
    (net (code "110") (name "/K14_LPUART1_TX") (class "Default")
      (node (ref "J1") (pin "17") (pinfunction "17_17") (pintype "passive"))
      (node (ref "U1") (pin "K14") (pinfunction "GPIO_AD_B0_12_K14") (pintype "bidirectional"))
    )
    (net (code "111") (name "/L5") (class "Default")
      (node (ref "J3") (pin "4") (pinfunction "4_4") (pintype "passive"))
      (node (ref "U1") (pin "L5") (pinfunction "GPIO_SD_B1_00_L5") (pintype "bidirectional"))
    )
    (net (code "112") (name "/L6_USER_BUTTON") (class "Default")
      (node (ref "J3") (pin "6") (pinfunction "6_6") (pintype "passive"))
      (node (ref "U1") (pin "L6") (pinfunction "WAKEUP_L6") (pintype "passive"))
    )
    (net (code "113") (name "/L7_PERI_PWREN") (class "Default")
      (node (ref "J3") (pin "8") (pinfunction "8_8") (pintype "passive"))
      (node (ref "U1") (pin "L7") (pinfunction "PMIC_STBY_REQ_L7") (pintype "passive"))
    )
    (net (code "114") (name "/L8_USB_OTG1_DP") (class "Default")
      (node (ref "J3") (pin "10") (pinfunction "10_10") (pintype "passive"))
      (node (ref "U1") (pin "L8") (pinfunction "USB_OTG1_DP_L8") (pintype "bidirectional"))
    )
    (net (code "115") (name "/L10") (class "Default")
      (node (ref "J1") (pin "26") (pinfunction "26_26") (pintype "passive"))
      (node (ref "U1") (pin "L10") (pinfunction "GPIO_AD_B0_15_L10") (pintype "bidirectional"))
    )
    (net (code "116") (name "/L11_LPUART2_TX") (class "Default")
      (node (ref "J3") (pin "14") (pinfunction "14_14") (pintype "passive"))
      (node (ref "U1") (pin "L11") (pinfunction "GPIO_AD_B1_02_L11") (pintype "bidirectional"))
    )
    (net (code "117") (name "/L12") (class "Default")
      (node (ref "J3") (pin "17") (pinfunction "17_17") (pintype "passive"))
      (node (ref "U1") (pin "L12") (pinfunction "GPIO_AD_B1_04_L12") (pintype "bidirectional"))
    )
    (net (code "118") (name "/L13") (class "Default")
      (node (ref "J1") (pin "15") (pinfunction "15_15") (pintype "passive"))
      (node (ref "U1") (pin "L13") (pinfunction "GPIO_AD_B1_10_L13") (pintype "bidirectional"))
    )
    (net (code "119") (name "/L14_LPUART1_RX") (class "Default")
      (node (ref "J1") (pin "18") (pinfunction "18_18") (pintype "passive"))
      (node (ref "U1") (pin "L14") (pinfunction "GPIO_AD_B0_13_L14") (pintype "bidirectional"))
    )
    (net (code "120") (name "/M3") (class "Default")
      (node (ref "J2") (pin "56") (pinfunction "56_56") (pintype "passive"))
      (node (ref "U1") (pin "M3") (pinfunction "GPIO_SD_B1_02_M3") (pintype "bidirectional"))
    )
    (net (code "121") (name "/M4") (class "Default")
      (node (ref "J3") (pin "2") (pinfunction "2_2") (pintype "passive"))
      (node (ref "U1") (pin "M4") (pinfunction "GPIO_SD_B1_03_M4") (pintype "bidirectional"))
    )
    (net (code "122") (name "/M5") (class "Default")
      (node (ref "J3") (pin "3") (pinfunction "3_3") (pintype "passive"))
      (node (ref "U1") (pin "M5") (pinfunction "GPIO_SD_B1_01_M5") (pintype "bidirectional"))
    )
    (net (code "123") (name "/M6_ONOFF") (class "Default")
      (node (ref "J3") (pin "5") (pinfunction "5_5") (pintype "passive"))
      (node (ref "U1") (pin "M6") (pinfunction "ONOFF_M6") (pintype "input"))
    )
    (net (code "124") (name "/M7_POR_B") (class "Default")
      (node (ref "C22") (pin "2") (pinfunction "2_2") (pintype "passive"))
      (node (ref "J3") (pin "7") (pinfunction "7_7") (pintype "passive"))
      (node (ref "R14") (pin "2") (pinfunction "2_2") (pintype "passive"))
      (node (ref "U1") (pin "M7") (pinfunction "~{POR}_M7") (pintype "passive"))
    )
    (net (code "125") (name "/M8_USB_OTG1_DN") (class "Default")
      (node (ref "J3") (pin "11") (pinfunction "11_11") (pintype "passive"))
      (node (ref "U1") (pin "M8") (pinfunction "USB_OTG1_DN_M8") (pintype "bidirectional"))
    )
    (net (code "126") (name "/M11_CAN2_TXD") (class "Default")
      (node (ref "J3") (pin "15") (pinfunction "15_15") (pintype "passive"))
      (node (ref "U1") (pin "M11") (pinfunction "GPIO_AD_B0_02_M11") (pintype "bidirectional"))
    )
    (net (code "127") (name "/M12_LPUART2_RX") (class "Default")
      (node (ref "J3") (pin "16") (pinfunction "16_16") (pintype "passive"))
      (node (ref "U1") (pin "M12") (pinfunction "GPIO_AD_B1_03_M12") (pintype "bidirectional"))
    )
    (net (code "128") (name "/M13_SAI1_MCLK") (class "Default")
      (node (ref "J1") (pin "13") (pinfunction "13_13") (pintype "passive"))
      (node (ref "U1") (pin "M13") (pinfunction "GPIO_AD_B1_09_M13") (pintype "bidirectional"))
    )
    (net (code "129") (name "/M14") (class "Default")
      (node (ref "J1") (pin "16") (pinfunction "16_16") (pintype "passive"))
      (node (ref "U1") (pin "M14") (pinfunction "GPIO_AD_B0_00_M14") (pintype "bidirectional"))
    )
    (net (code "130") (name "/N3") (class "Default")
      (node (ref "J2") (pin "57") (pinfunction "57_57") (pintype "passive"))
      (node (ref "U1") (pin "N3") (pinfunction "GPIO_SD_B1_05_N3") (pintype "bidirectional"))
    )
    (net (code "131") (name "/N7_USB_OTG2_DN") (class "Default")
      (node (ref "J3") (pin "12") (pinfunction "12_12") (pintype "passive"))
      (node (ref "U1") (pin "N7") (pinfunction "USB_OTG2_DN_N7") (pintype "bidirectional"))
    )
    (net (code "132") (name "/N12_USB_OTG1_CHD") (class "Default")
      (node (ref "J1") (pin "14") (pinfunction "14_14") (pintype "passive"))
      (node (ref "U1") (pin "N12") (pinfunction "~{USB_OTG1_CHD}_N12") (pintype "bidirectional"))
    )
    (net (code "133") (name "/P2") (class "Default")
      (node (ref "J2") (pin "58") (pinfunction "58_58") (pintype "passive"))
      (node (ref "U1") (pin "P2") (pinfunction "GPIO_SD_B1_04_P2") (pintype "bidirectional"))
    )
    (net (code "134") (name "/P7_USB_OTG2_DP") (class "Default")
      (node (ref "J3") (pin "13") (pinfunction "13_13") (pintype "passive"))
      (node (ref "U1") (pin "P7") (pinfunction "USB_OTG2_DP_P7") (pintype "bidirectional"))
    )
    (net (code "137") (name "5V_USB_OTG1_VBUS") (class "Default")
      (node (ref "J3") (pin "21") (pinfunction "21_21") (pintype "passive"))
      (node (ref "R22") (pin "1") (pinfunction "1_1") (pintype "passive"))
    )
    (net (code "138") (name "5V_USB_OTG2_VBUS") (class "Default")
      (node (ref "J3") (pin "22") (pinfunction "22_22") (pintype "passive"))
      (node (ref "R10") (pin "1") (pinfunction "1_1") (pintype "passive"))
      (node (ref "R23") (pin "1") (pinfunction "1_1") (pintype "passive"))
    )
    (net (code "139") (name "DCDC_3V3") (class "Default")
      (node (ref "C60") (pin "1") (pinfunction "1_1") (pintype "passive"))
      (node (ref "R11") (pin "1") (pinfunction "1_1") (pintype "passive"))
      (node (ref "R37") (pin "2") (pinfunction "2_2") (pintype "passive"))
      (node (ref "R8") (pin "2") (pinfunction "2_2") (pintype "passive"))
    )
    (net (code "140") (name "DCDC_OUT") (class "Default")
      (node (ref "C29") (pin "2") (pinfunction "2_2") (pintype "passive"))
      (node (ref "C30") (pin "1") (pinfunction "1_1") (pintype "passive"))
      (node (ref "L1") (pin "2") (pintype "passive"))
      (node (ref "R2") (pin "2") (pinfunction "2_2") (pintype "passive"))
    )
    (net (code "141") (name "FLASH_VCC") (class "Default")
      (node (ref "C52") (pin "2") (pinfunction "2_2") (pintype "passive"))
      (node (ref "C53") (pin "2") (pinfunction "2_2") (pintype "passive"))
      (node (ref "R25") (pin "2") (pinfunction "2_2") (pintype "passive"))
      (node (ref "R26") (pin "1") (pinfunction "1_1") (pintype "passive"))
      (node (ref "R27") (pin "1") (pinfunction "1_1") (pintype "passive"))
      (node (ref "R28") (pin "1") (pinfunction "1_1") (pintype "passive"))
      (node (ref "U3") (pin "8") (pinfunction "VCC_8") (pintype "power_in"))
    )
    (net (code "142") (name "GND") (class "Default")
      (node (ref "C1") (pin "2") (pinfunction "2_2") (pintype "passive"))
      (node (ref "C10") (pin "2") (pinfunction "2_2") (pintype "passive"))
      (node (ref "C11") (pin "2") (pinfunction "2_2") (pintype "passive"))
      (node (ref "C12") (pin "1") (pinfunction "1_1") (pintype "passive"))
      (node (ref "C13") (pin "1") (pinfunction "1_1") (pintype "passive"))
      (node (ref "C14") (pin "1") (pinfunction "1_1") (pintype "passive"))
      (node (ref "C15") (pin "2") (pinfunction "2_2") (pintype "passive"))
      (node (ref "C16") (pin "1") (pinfunction "1_1") (pintype "passive"))
      (node (ref "C17") (pin "2") (pinfunction "2_2") (pintype "passive"))
      (node (ref "C18") (pin "1") (pinfunction "1_1") (pintype "passive"))
      (node (ref "C19") (pin "2") (pinfunction "2_2") (pintype "passive"))
      (node (ref "C2") (pin "2") (pinfunction "2_2") (pintype "passive"))
      (node (ref "C20") (pin "1") (pinfunction "1_1") (pintype "passive"))
      (node (ref "C21") (pin "2") (pinfunction "2_2") (pintype "passive"))
      (node (ref "C22") (pin "1") (pinfunction "1_1") (pintype "passive"))
      (node (ref "C23") (pin "1") (pinfunction "1_1") (pintype "passive"))
      (node (ref "C24") (pin "1") (pinfunction "1_1") (pintype "passive"))
      (node (ref "C25") (pin "2") (pinfunction "2_2") (pintype "passive"))
      (node (ref "C26") (pin "2") (pinfunction "2_2") (pintype "passive"))
      (node (ref "C27") (pin "2") (pinfunction "2_2") (pintype "passive"))
      (node (ref "C28") (pin "2") (pinfunction "2_2") (pintype "passive"))
      (node (ref "C29") (pin "1") (pinfunction "1_1") (pintype "passive"))
      (node (ref "C3") (pin "2") (pinfunction "2_2") (pintype "passive"))
      (node (ref "C30") (pin "2") (pinfunction "2_2") (pintype "passive"))
      (node (ref "C31") (pin "1") (pinfunction "1_1") (pintype "passive"))
      (node (ref "C32") (pin "1") (pinfunction "1_1") (pintype "passive"))
      (node (ref "C33") (pin "1") (pinfunction "1_1") (pintype "passive"))
      (node (ref "C34") (pin "1") (pinfunction "1_1") (pintype "passive"))
      (node (ref "C35") (pin "2") (pinfunction "2_2") (pintype "passive"))
      (node (ref "C36") (pin "1") (pinfunction "1_1") (pintype "passive"))
      (node (ref "C37") (pin "1") (pinfunction "1_1") (pintype "passive"))
      (node (ref "C38") (pin "1") (pinfunction "1_1") (pintype "passive"))
      (node (ref "C39") (pin "1") (pinfunction "1_1") (pintype "passive"))
      (node (ref "C4") (pin "2") (pinfunction "2_2") (pintype "passive"))
      (node (ref "C40") (pin "1") (pinfunction "1_1") (pintype "passive"))
      (node (ref "C41") (pin "1") (pinfunction "1_1") (pintype "passive"))
      (node (ref "C42") (pin "1") (pinfunction "1_1") (pintype "passive"))
      (node (ref "C43") (pin "1") (pinfunction "1_1") (pintype "passive"))
      (node (ref "C44") (pin "1") (pinfunction "1_1") (pintype "passive"))
      (node (ref "C45") (pin "1") (pinfunction "1_1") (pintype "passive"))
      (node (ref "C46") (pin "1") (pinfunction "1_1") (pintype "passive"))
      (node (ref "C47") (pin "1") (pinfunction "1_1") (pintype "passive"))
      (node (ref "C48") (pin "1") (pinfunction "1_1") (pintype "passive"))
      (node (ref "C49") (pin "1") (pinfunction "1_1") (pintype "passive"))
      (node (ref "C5") (pin "2") (pinfunction "2_2") (pintype "passive"))
      (node (ref "C50") (pin "1") (pinfunction "1_1") (pintype "passive"))
      (node (ref "C51") (pin "1") (pinfunction "1_1") (pintype "passive"))
      (node (ref "C52") (pin "1") (pinfunction "1_1") (pintype "passive"))
      (node (ref "C53") (pin "1") (pinfunction "1_1") (pintype "passive"))
      (node (ref "C6") (pin "2") (pinfunction "2_2") (pintype "passive"))
      (node (ref "C60") (pin "2") (pinfunction "2_2") (pintype "passive"))
      (node (ref "C7") (pin "2") (pinfunction "2_2") (pintype "passive"))
      (node (ref "C8") (pin "2") (pinfunction "2_2") (pintype "passive"))
      (node (ref "C9") (pin "2") (pinfunction "2_2") (pintype "passive"))
      (node (ref "J1") (pin "1") (pinfunction "1_1") (pintype "passive"))
      (node (ref "J1") (pin "2") (pinfunction "2_2") (pintype "passive"))
      (node (ref "J1") (pin "59") (pinfunction "59_59") (pintype "passive"))
      (node (ref "J1") (pin "60") (pinfunction "60_60") (pintype "passive"))
      (node (ref "J2") (pin "1") (pinfunction "1_1") (pintype "passive"))
      (node (ref "J2") (pin "2") (pinfunction "2_2") (pintype "passive"))
      (node (ref "J2") (pin "59") (pinfunction "59_59") (pintype "passive"))
      (node (ref "J2") (pin "60") (pinfunction "60_60") (pintype "passive"))
      (node (ref "J3") (pin "1") (pinfunction "1_1") (pintype "passive"))
      (node (ref "J3") (pin "18") (pinfunction "18_18") (pintype "passive"))
      (node (ref "J3") (pin "25") (pinfunction "25_25") (pintype "passive"))
      (node (ref "LED1") (pin "2") (pinfunction "2_2") (pintype "passive"))
      (node (ref "LED2") (pin "2") (pinfunction "2_2") (pintype "passive"))
      (node (ref "R17") (pin "1") (pinfunction "1_1") (pintype "passive"))
      (node (ref "R21") (pin "1") (pinfunction "1_1") (pintype "passive"))
      (node (ref "R35") (pin "1") (pinfunction "1_1") (pintype "passive"))
      (node (ref "R36") (pin "2") (pinfunction "2_2") (pintype "passive"))
      (node (ref "U1") (pin "A1") (pinfunction "VSS1_A1") (pintype "power_in"))
      (node (ref "U1") (pin "A14") (pinfunction "VSS2_A14") (pintype "power_in"))
      (node (ref "U1") (pin "B10") (pinfunction "VSS4_B10") (pintype "power_in"))
      (node (ref "U1") (pin "B5") (pinfunction "VSS3_B5") (pintype "power_in"))
      (node (ref "U1") (pin "E13") (pinfunction "VSS6_E13") (pintype "power_in"))
      (node (ref "U1") (pin "E2") (pinfunction "VSS5_E2") (pintype "power_in"))
      (node (ref "U1") (pin "G7") (pinfunction "VSS7_G7") (pintype "power_in"))
      (node (ref "U1") (pin "G8") (pinfunction "VSS8_G8") (pintype "power_in"))
      (node (ref "U1") (pin "H7") (pinfunction "VSS9_H7") (pintype "power_in"))
      (node (ref "U1") (pin "H8") (pinfunction "VSS10_H8") (pintype "power_in"))
      (node (ref "U1") (pin "J7") (pinfunction "VSS11_J7") (pintype "power_in"))
      (node (ref "U1") (pin "J8") (pinfunction "VSS12_J8") (pintype "power_in"))
      (node (ref "U1") (pin "K13") (pinfunction "VSS14_K13") (pintype "power_in"))
      (node (ref "U1") (pin "K2") (pinfunction "VSS13_K2") (pintype "power_in"))
      (node (ref "U1") (pin "K6") (pinfunction "TEST_MODE_K6") (pintype "passive"))
      (node (ref "U1") (pin "K9") (pinfunction "NGND_KEL0_K9") (pintype "power_in"))
      (node (ref "U1") (pin "L9") (pinfunction "VSS15_L9") (pintype "power_in"))
      (node (ref "U1") (pin "N1") (pinfunction "DCDC_GND_1_N1") (pintype "power_in"))
      (node (ref "U1") (pin "N2") (pinfunction "DCDC_GND_2_N2") (pintype "power_in"))
      (node (ref "U1") (pin "N5") (pinfunction "VSS16_N5") (pintype "power_in"))
      (node (ref "U1") (pin "N8") (pinfunction "VSS17_N8") (pintype "power_in"))
      (node (ref "U1") (pin "P1") (pinfunction "VSS18_P1") (pintype "power_in"))
      (node (ref "U1") (pin "P14") (pinfunction "VSS19_P14") (pintype "power_in"))
      (node (ref "U2") (pin "1") (pinfunction "GND_1") (pintype "power_in"))
      (node (ref "U3") (pin "4") (pinfunction "GND_4") (pintype "power_in"))
      (node (ref "Y1") (pin "2") (pinfunction "GND2_2") (pintype "passive"))
    )
    (net (code "143") (name "MCU_DCDC_IN") (class "Default")
      (node (ref "C24") (pin "2") (pinfunction "2_2") (pintype "passive"))
      (node (ref "C25") (pin "1") (pinfunction "1_1") (pintype "passive"))
      (node (ref "C26") (pin "1") (pinfunction "1_1") (pintype "passive"))
      (node (ref "C27") (pin "1") (pinfunction "1_1") (pintype "passive"))
      (node (ref "C28") (pin "1") (pinfunction "1_1") (pintype "passive"))
      (node (ref "R15") (pin "1") (pinfunction "1_1") (pintype "passive"))
      (node (ref "R18") (pin "2") (pinfunction "2_2") (pintype "passive"))
      (node (ref "U1") (pin "K4") (pinfunction "DCDC_IN_Q_K4") (pintype "passive"))
      (node (ref "U1") (pin "L1") (pinfunction "DCDC_IN_1_L1") (pintype "passive"))
      (node (ref "U1") (pin "L2") (pinfunction "DCDC_IN_2_L2") (pintype "passive"))
    )
    (net (code "144") (name "MCU_DCDC_IN_3V3") (class "Default")
      (node (ref "R15") (pin "2") (pinfunction "2_2") (pintype "passive"))
      (node (ref "R7") (pin "2") (pinfunction "2_2") (pintype "passive"))
    )
    (net (code "145") (name "NVCC_GPIO_3V3") (class "Default")
      (node (ref "C39") (pin "2") (pinfunction "2_2") (pintype "passive"))
      (node (ref "C40") (pin "2") (pinfunction "2_2") (pintype "passive"))
      (node (ref "C41") (pin "2") (pinfunction "2_2") (pintype "passive"))
      (node (ref "C42") (pin "2") (pinfunction "2_2") (pintype "passive"))
      (node (ref "R20") (pin "2") (pinfunction "2_2") (pintype "passive"))
      (node (ref "U1") (pin "E9") (pinfunction "NVCC_GPIO_1_E9") (pintype "power_in"))
      (node (ref "U1") (pin "F10") (pinfunction "NVCC_GPIO_2_F10") (pintype "power_in"))
      (node (ref "U1") (pin "J10") (pinfunction "NVCC_GPIO_3_J10") (pintype "power_in"))
    )
    (net (code "146") (name "NVCC_SD") (class "Default")
      (node (ref "C47") (pin "2") (pinfunction "2_2") (pintype "passive"))
      (node (ref "C48") (pin "2") (pinfunction "2_2") (pintype "passive"))
      (node (ref "C50") (pin "2") (pinfunction "2_2") (pintype "passive"))
      (node (ref "C51") (pin "2") (pinfunction "2_2") (pintype "passive"))
      (node (ref "R24") (pin "1") (pinfunction "1_1") (pintype "passive"))
      (node (ref "U1") (pin "J6") (pinfunction "NVCC_SD0_J6") (pintype "power_in"))
      (node (ref "U1") (pin "K5") (pinfunction "NVCC_SD1_K5") (pintype "power_in"))
    )
    (net (code "147") (name "NVCC_SEMC_3V3") (class "Default")
      (node (ref "C36") (pin "2") (pinfunction "2_2") (pintype "passive"))
      (node (ref "C37") (pin "2") (pinfunction "2_2") (pintype "passive"))
      (node (ref "C38") (pin "2") (pinfunction "2_2") (pintype "passive"))
      (node (ref "R19") (pin "2") (pinfunction "2_2") (pintype "passive"))
      (node (ref "U1") (pin "E6") (pinfunction "NVCC_EMC_1_E6") (pintype "power_in"))
      (node (ref "U1") (pin "F5") (pinfunction "NVCC_EMC_2_F5") (pintype "power_in"))
    )
    (net (code "148") (name "Net-(LED1-Pad1)") (class "Default")
      (node (ref "LED1") (pin "1") (pinfunction "1_1") (pintype "passive"))
      (node (ref "R9") (pin "2") (pinfunction "2_2") (pintype "passive"))
    )
    (net (code "149") (name "Net-(LED2-Pad1)") (class "Default")
      (node (ref "LED2") (pin "1") (pinfunction "1_1") (pintype "passive"))
      (node (ref "R10") (pin "2") (pinfunction "2_2") (pintype "passive"))
    )
    (net (code "150") (name "Net-(R11-Pad2)") (class "Default")
      (node (ref "R11") (pin "2") (pinfunction "2_2") (pintype "passive"))
      (node (ref "R12") (pin "1") (pinfunction "1_1") (pintype "passive"))
    )
    (net (code "151") (name "Net-(U1A-NVCC_PLL)") (class "Default")
      (node (ref "C18") (pin "2") (pinfunction "2_2") (pintype "passive"))
      (node (ref "C19") (pin "1") (pinfunction "1_1") (pintype "passive"))
      (node (ref "U1") (pin "P10") (pinfunction "NVCC_PLL_P10") (pintype "power_in"))
    )
    (net (code "152") (name "Net-(U1A-VDDA_ADC_3P3)") (class "Default")
      (node (ref "C1") (pin "1") (pinfunction "1_1") (pintype "passive"))
      (node (ref "C2") (pin "1") (pinfunction "1_1") (pintype "passive"))
      (node (ref "R1") (pin "2") (pinfunction "2_2") (pintype "passive"))
      (node (ref "U1") (pin "N14") (pinfunction "VDDA_ADC_3P3_N14") (pintype "power_in"))
    )
    (net (code "153") (name "Net-(U1A-VDD_HIGH_CAP)") (class "Default")
      (node (ref "C16") (pin "2") (pinfunction "2_2") (pintype "passive"))
      (node (ref "C17") (pin "1") (pinfunction "1_1") (pintype "passive"))
      (node (ref "U1") (pin "P8") (pinfunction "VDD_HIGH_CAP_P8") (pintype "power_in"))
    )
    (net (code "154") (name "Net-(U1A-VDD_HIGH_IN)") (class "Default")
      (node (ref "C14") (pin "2") (pinfunction "2_2") (pintype "passive"))
      (node (ref "C15") (pin "1") (pinfunction "1_1") (pintype "passive"))
      (node (ref "R3") (pin "2") (pinfunction "2_2") (pintype "passive"))
      (node (ref "U1") (pin "P12") (pinfunction "VDD_HIGH_IN_P12") (pintype "power_in"))
    )
    (net (code "155") (name "Net-(U1A-VDD_SNVS_CAP)") (class "Default")
      (node (ref "C21") (pin "1") (pinfunction "1_1") (pintype "passive"))
      (node (ref "U1") (pin "M10") (pinfunction "VDD_SNVS_CAP_M10") (pintype "power_in"))
    )
    (net (code "156") (name "Net-(U1B-DCDC_LP_1)") (class "Default")
      (node (ref "L1") (pin "1") (pintype "passive"))
      (node (ref "U1") (pin "M1") (pinfunction "DCDC_LP_1_M1") (pintype "passive"))
      (node (ref "U1") (pin "M2") (pinfunction "DCDC_LP_2_M2") (pintype "passive"))
    )
    (net (code "157") (name "Net-(U1B-DCDC_PSWITCH)") (class "Default")
      (node (ref "C35") (pin "1") (pinfunction "1_1") (pintype "passive"))
      (node (ref "R18") (pin "1") (pinfunction "1_1") (pintype "passive"))
      (node (ref "U1") (pin "K3") (pinfunction "DCDC_PSWITCH_K3") (pintype "passive"))
    )
    (net (code "158") (name "Net-(U1B-GPANAIO)") (class "Default")
      (node (ref "GPANIO1") (pin "1") (pinfunction "1_1") (pintype "passive"))
      (node (ref "U1") (pin "N10") (pinfunction "GPANAIO_N10") (pintype "power_in"))
    )
    (net (code "159") (name "Net-(U1B-RTC_XTALI)") (class "Default")
      (node (ref "C33") (pin "2") (pinfunction "2_2") (pintype "passive"))
      (node (ref "U1") (pin "N9") (pinfunction "RTC_XTALI_N9") (pintype "input"))
      (node (ref "Y2") (pin "1") (pinfunction "1_1") (pintype "passive"))
    )
    (net (code "160") (name "Net-(U1B-RTC_XTALO)") (class "Default")
      (node (ref "C34") (pin "2") (pinfunction "2_2") (pintype "passive"))
      (node (ref "U1") (pin "P9") (pinfunction "RTC_XTALO_P9") (pintype "output"))
      (node (ref "Y2") (pin "2") (pinfunction "2_2") (pintype "passive"))
    )
    (net (code "161") (name "Net-(U1B-XTALI)") (class "Default")
      (node (ref "C32") (pin "2") (pinfunction "2_2") (pintype "passive"))
      (node (ref "R16") (pin "2") (pinfunction "2_2") (pintype "passive"))
      (node (ref "R17") (pin "2") (pinfunction "2_2") (pintype "passive"))
      (node (ref "U1") (pin "P11") (pinfunction "XTALI_P11") (pintype "input"))
      (node (ref "Y1") (pin "3") (pinfunction "OSC2_3") (pintype "passive"))
    )
    (net (code "162") (name "Net-(U1B-XTALO)") (class "Default")
      (node (ref "C31") (pin "2") (pinfunction "2_2") (pintype "passive"))
      (node (ref "R16") (pin "1") (pinfunction "1_1") (pintype "passive"))
      (node (ref "R6") (pin "2") (pinfunction "2_2") (pintype "passive"))
      (node (ref "U1") (pin "N11") (pinfunction "XTALO_N11") (pintype "output"))
    )
    (net (code "163") (name "Net-(U1C-USB_OTG1_VBUS)") (class "Default")
      (node (ref "C44") (pin "2") (pinfunction "2_2") (pintype "passive"))
      (node (ref "R22") (pin "2") (pinfunction "2_2") (pintype "passive"))
      (node (ref "U1") (pin "N6") (pinfunction "USB_OTG1_VBUS_N6") (pintype "power_in"))
    )
    (net (code "164") (name "Net-(U1C-USB_OTG2_VBUS)") (class "Default")
      (node (ref "C49") (pin "2") (pinfunction "2_2") (pintype "passive"))
      (node (ref "R23") (pin "2") (pinfunction "2_2") (pintype "passive"))
      (node (ref "U1") (pin "P6") (pinfunction "USB_OTG2_VBUS_P6") (pintype "power_in"))
    )
    (net (code "165") (name "Net-(U2-VCC)") (class "Default")
      (node (ref "C23") (pin "2") (pinfunction "2_2") (pintype "passive"))
      (node (ref "R12") (pin "2") (pinfunction "2_2") (pintype "passive"))
      (node (ref "R13") (pin "1") (pinfunction "1_1") (pintype "passive"))
      (node (ref "U2") (pin "3") (pinfunction "VCC_3") (pintype "power_in"))
    )
    (net (code "166") (name "Net-(U2-~{RESET})") (class "Default")
      (node (ref "R13") (pin "2") (pinfunction "2_2") (pintype "passive"))
      (node (ref "R14") (pin "1") (pinfunction "1_1") (pintype "passive"))
      (node (ref "U2") (pin "2") (pinfunction "~{RESET}_2") (pintype "open_collector"))
    )
    (net (code "167") (name "Net-(U3-SCK)") (class "Default")
      (node (ref "R34") (pin "2") (pinfunction "2_2") (pintype "passive"))
      (node (ref "U3") (pin "6") (pinfunction "SCK_6") (pintype "input"))
    )
    (net (code "168") (name "Net-(U3-SI_IO0)") (class "Default")
      (node (ref "R29") (pin "1") (pinfunction "1_1") (pintype "passive"))
      (node (ref "U3") (pin "5") (pinfunction "SI_IO0_5") (pintype "bidirectional"))
    )
    (net (code "169") (name "Net-(U3-SO_IO1)") (class "Default")
      (node (ref "R31") (pin "1") (pinfunction "1_1") (pintype "passive"))
      (node (ref "U3") (pin "2") (pinfunction "SO_IO1_2") (pintype "bidirectional"))
    )
    (net (code "170") (name "Net-(U3-~{CE})") (class "Default")
      (node (ref "R28") (pin "2") (pinfunction "2_2") (pintype "passive"))
      (node (ref "R30") (pin "2") (pinfunction "2_2") (pintype "passive"))
      (node (ref "U3") (pin "1") (pinfunction "~{CE}_1") (pintype "input"))
    )
    (net (code "171") (name "Net-(U3-~{HOLD}{slash}~{RESET}_IO3)") (class "Default")
      (node (ref "R26") (pin "2") (pinfunction "2_2") (pintype "passive"))
      (node (ref "R33") (pin "1") (pinfunction "1_1") (pintype "passive"))
      (node (ref "U3") (pin "7") (pinfunction "~{HOLD}/~{RESET}_IO3_7") (pintype "bidirectional"))
    )
    (net (code "172") (name "Net-(U3-~{WP}_IO2)") (class "Default")
      (node (ref "R27") (pin "2") (pinfunction "2_2") (pintype "passive"))
      (node (ref "R32") (pin "1") (pinfunction "1_1") (pintype "passive"))
      (node (ref "U3") (pin "3") (pinfunction "~{WP}_IO2_3") (pintype "bidirectional"))
    )
    (net (code "173") (name "Net-(Y1-GND1)") (class "Default")
      (node (ref "R36") (pin "1") (pinfunction "1_1") (pintype "passive"))
      (node (ref "R37") (pin "1") (pinfunction "1_1") (pintype "passive"))
      (node (ref "Y1") (pin "4") (pinfunction "GND1_4") (pintype "passive"))
    )
    (net (code "174") (name "Net-(Y1-OSC1)") (class "Default")
      (node (ref "R35") (pin "2") (pinfunction "2_2") (pintype "passive"))
      (node (ref "R6") (pin "1") (pinfunction "1_1") (pintype "passive"))
      (node (ref "Y1") (pin "1") (pinfunction "OSC1_1") (pintype "passive"))
    )
    (net (code "175") (name "VCC33") (class "Default")
      (node (ref "J3") (pin "19") (pinfunction "19_19") (pintype "passive"))
      (node (ref "J3") (pin "20") (pinfunction "20_20") (pintype "passive"))
      (node (ref "R19") (pin "1") (pinfunction "1_1") (pintype "passive"))
      (node (ref "R20") (pin "1") (pinfunction "1_1") (pintype "passive"))
      (node (ref "R24") (pin "2") (pinfunction "2_2") (pintype "passive"))
      (node (ref "R25") (pin "1") (pinfunction "1_1") (pintype "passive"))
      (node (ref "R4") (pin "1") (pinfunction "1_1") (pintype "passive"))
      (node (ref "R5") (pin "1") (pinfunction "1_1") (pintype "passive"))
      (node (ref "R7") (pin "1") (pinfunction "1_1") (pintype "passive"))
      (node (ref "R8") (pin "1") (pinfunction "1_1") (pintype "passive"))
      (node (ref "R9") (pin "1") (pinfunction "1_1") (pintype "passive"))
    )
    (net (code "176") (name "VDDA_ADC_3V3") (class "Default")
      (node (ref "R1") (pin "1") (pinfunction "1_1") (pintype "passive"))
      (node (ref "R4") (pin "2") (pinfunction "2_2") (pintype "passive"))
    )
    (net (code "177") (name "VDD_HIGH_IN_3V3") (class "Default")
      (node (ref "R3") (pin "1") (pinfunction "1_1") (pintype "passive"))
      (node (ref "R5") (pin "2") (pinfunction "2_2") (pintype "passive"))
    )
    (net (code "178") (name "VDD_SNVS_IN") (class "Default")
      (node (ref "C20") (pin "2") (pinfunction "2_2") (pintype "passive"))
      (node (ref "J3") (pin "23") (pinfunction "23_23") (pintype "passive"))
      (node (ref "J3") (pin "24") (pinfunction "24_24") (pintype "passive"))
      (node (ref "U1") (pin "M9") (pinfunction "VDD_SNVS_IN_M9") (pintype "power_in"))
    )
    (net (code "179") (name "VDD_SOC_IN") (class "Default")
      (node (ref "C10") (pin "1") (pinfunction "1_1") (pintype "passive"))
      (node (ref "C11") (pin "1") (pinfunction "1_1") (pintype "passive"))
      (node (ref "C12") (pin "2") (pinfunction "2_2") (pintype "passive"))
      (node (ref "C13") (pin "2") (pinfunction "2_2") (pintype "passive"))
      (node (ref "C3") (pin "1") (pinfunction "1_1") (pintype "passive"))
      (node (ref "C4") (pin "1") (pinfunction "1_1") (pintype "passive"))
      (node (ref "C5") (pin "1") (pinfunction "1_1") (pintype "passive"))
      (node (ref "C6") (pin "1") (pinfunction "1_1") (pintype "passive"))
      (node (ref "C7") (pin "1") (pinfunction "1_1") (pintype "passive"))
      (node (ref "C8") (pin "1") (pinfunction "1_1") (pintype "passive"))
      (node (ref "C9") (pin "1") (pinfunction "1_1") (pintype "passive"))
      (node (ref "R2") (pin "1") (pinfunction "1_1") (pintype "passive"))
      (node (ref "U1") (pin "F6") (pinfunction "VDD_SOC_IN_1_F6") (pintype "power_in"))
      (node (ref "U1") (pin "F7") (pinfunction "VDD_SOC_IN_2_F7") (pintype "power_in"))
      (node (ref "U1") (pin "F8") (pinfunction "VDD_SOC_IN_3_F8") (pintype "power_in"))
      (node (ref "U1") (pin "F9") (pinfunction "VDD_SOC_IN_4_F9") (pintype "power_in"))
      (node (ref "U1") (pin "G6") (pinfunction "VDD_SOC_IN_5_G6") (pintype "power_in"))
      (node (ref "U1") (pin "G9") (pinfunction "VDD_SOC_IN_6_G9") (pintype "power_in"))
      (node (ref "U1") (pin "H6") (pinfunction "VDD_SOC_IN_7_H6") (pintype "power_in"))
      (node (ref "U1") (pin "H9") (pinfunction "VDD_SOC_IN_8_H9") (pintype "power_in"))
      (node (ref "U1") (pin "J5") (pinfunction "DCDC_SENSE_J5") (pintype "passive"))
      (node (ref "U1") (pin "J9") (pinfunction "VDD_SOC_IN_9_J9") (pintype "power_in"))
    )
    (net (code "180") (name "VDD_USB_3V") (class "Default")
      (node (ref "C45") (pin "2") (pinfunction "2_2") (pintype "passive"))
      (node (ref "C46") (pin "2") (pinfunction "2_2") (pintype "passive"))
      (node (ref "U1") (pin "K8") (pinfunction "VDD_USB_CAP_K8") (pintype "power_in"))
    )
    (net (code "181") (name "unconnected-(U1B-CCM_CLK1_N-PadP13)") (class "Default")
      (node (ref "U1") (pin "P13") (pinfunction "CCM_CLK1_N_P13") (pintype "passive"))
    )
    (net (code "182") (name "unconnected-(U1B-CCM_CLK1_P-PadN13)") (class "Default")
      (node (ref "U1") (pin "N13") (pinfunction "CCM_CLK1_P_N13") (pintype "passive"))
    )
  )
)
